# OpenROV_Controller_2_8.net
KiCad netlist of a schematic drawn in EAGLE
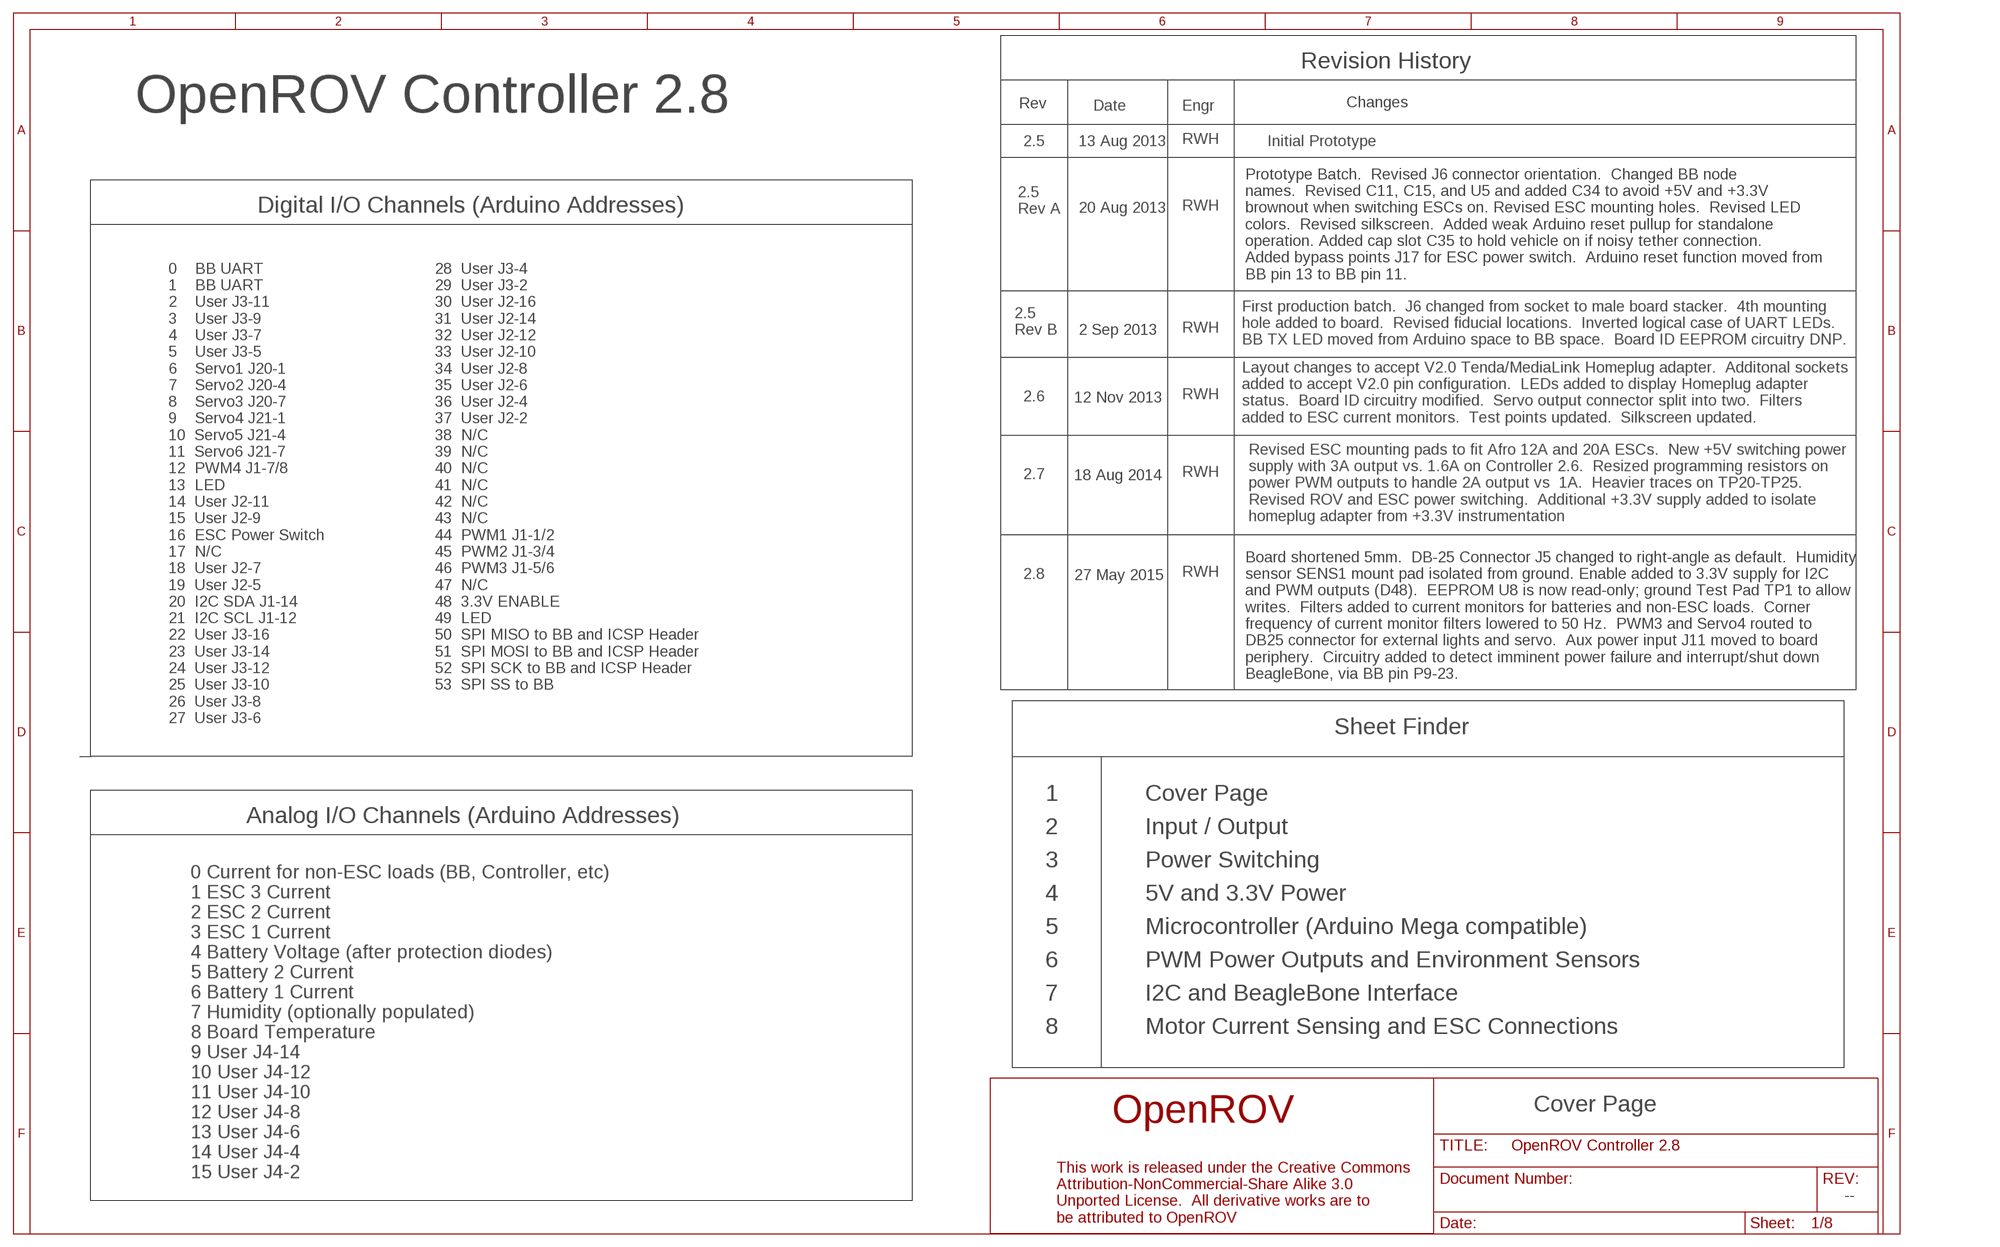
[diagram p0: schematic, sheet 1]
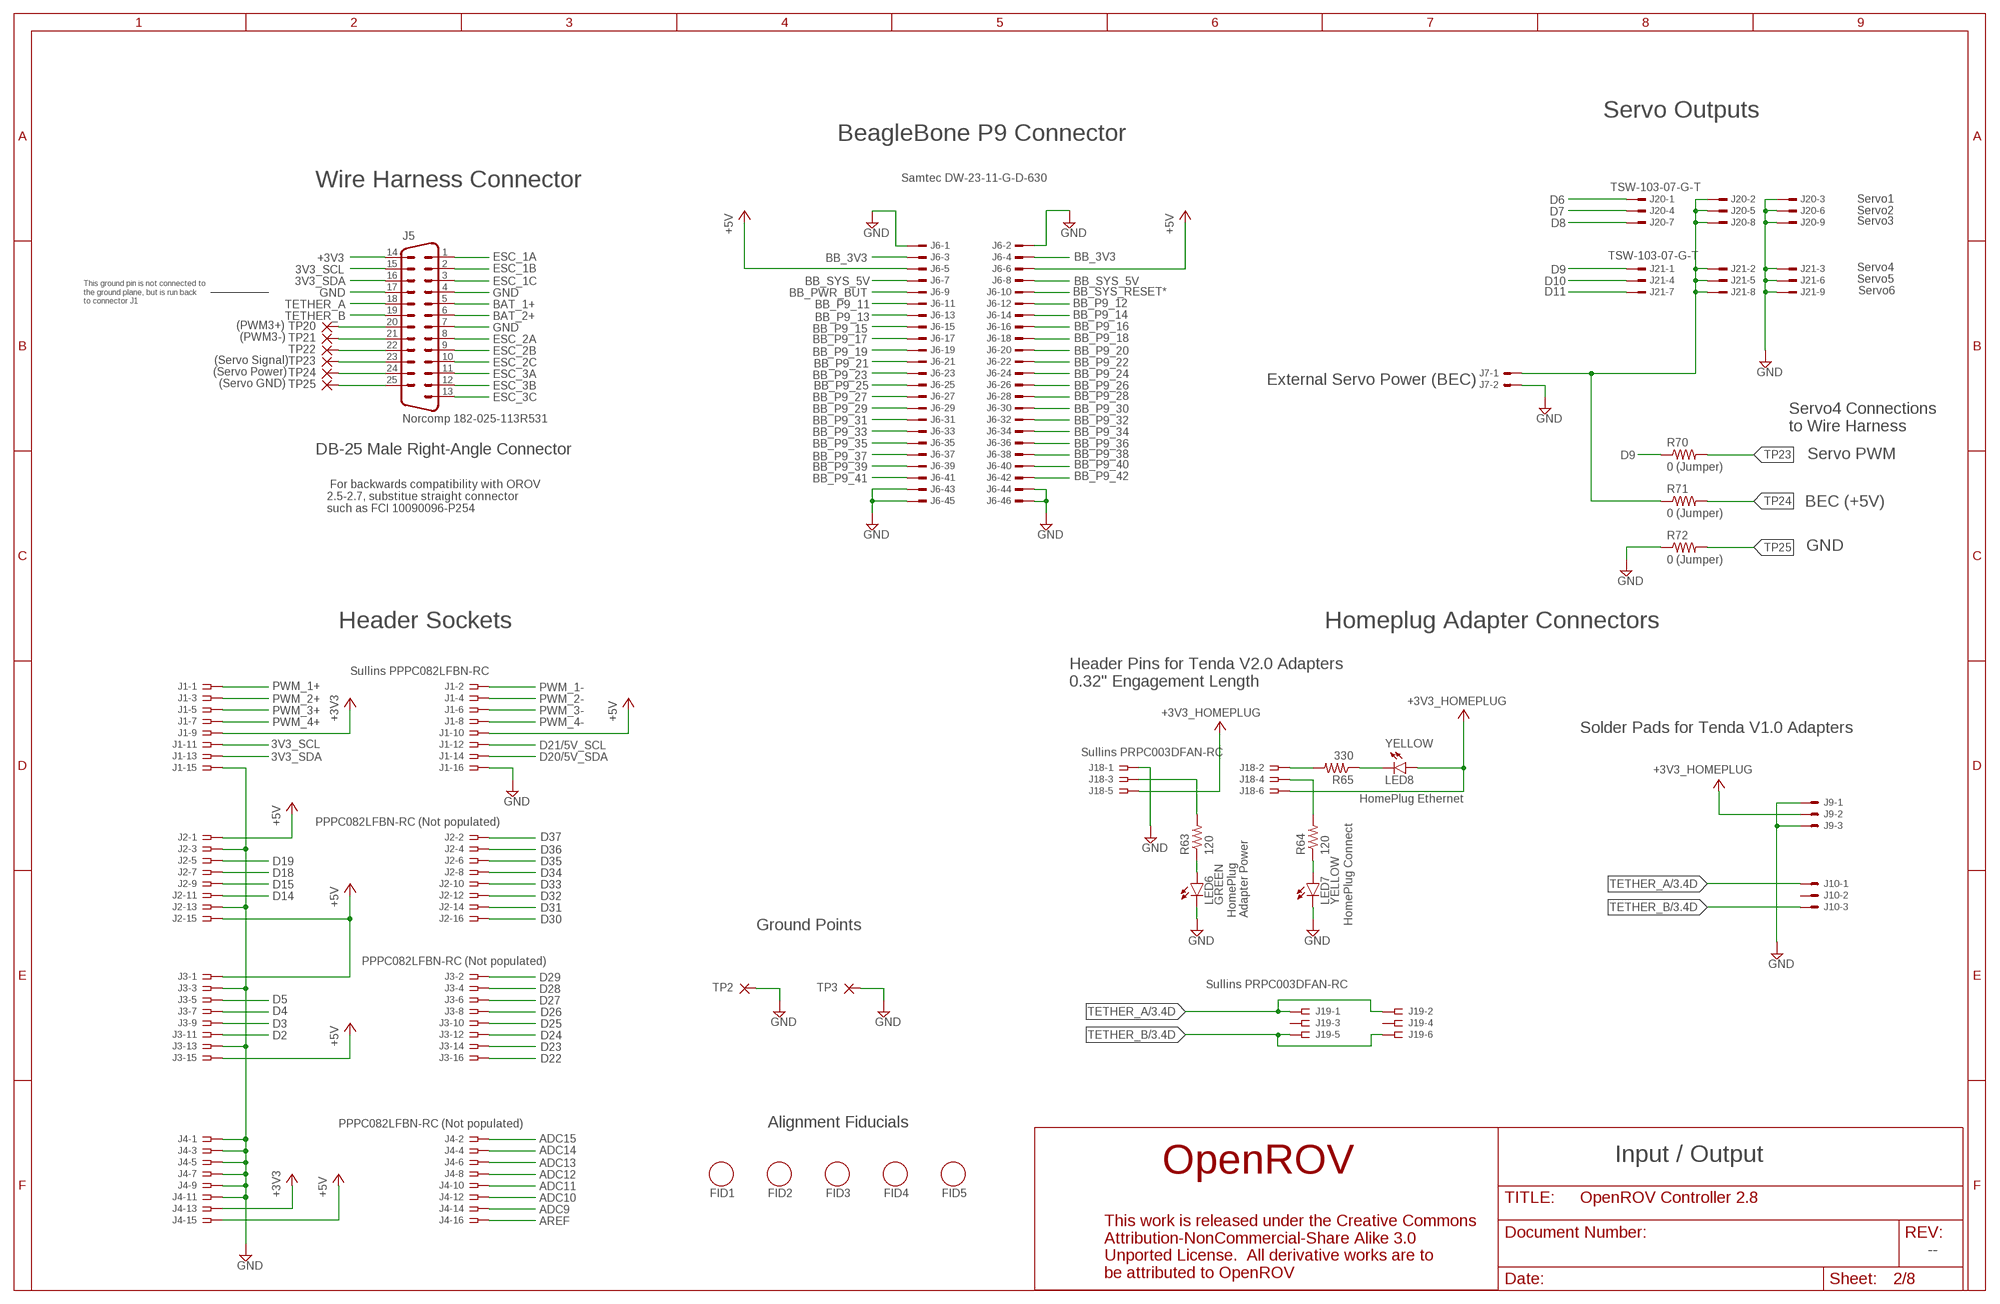
[diagram p1: schematic, sheet 2]
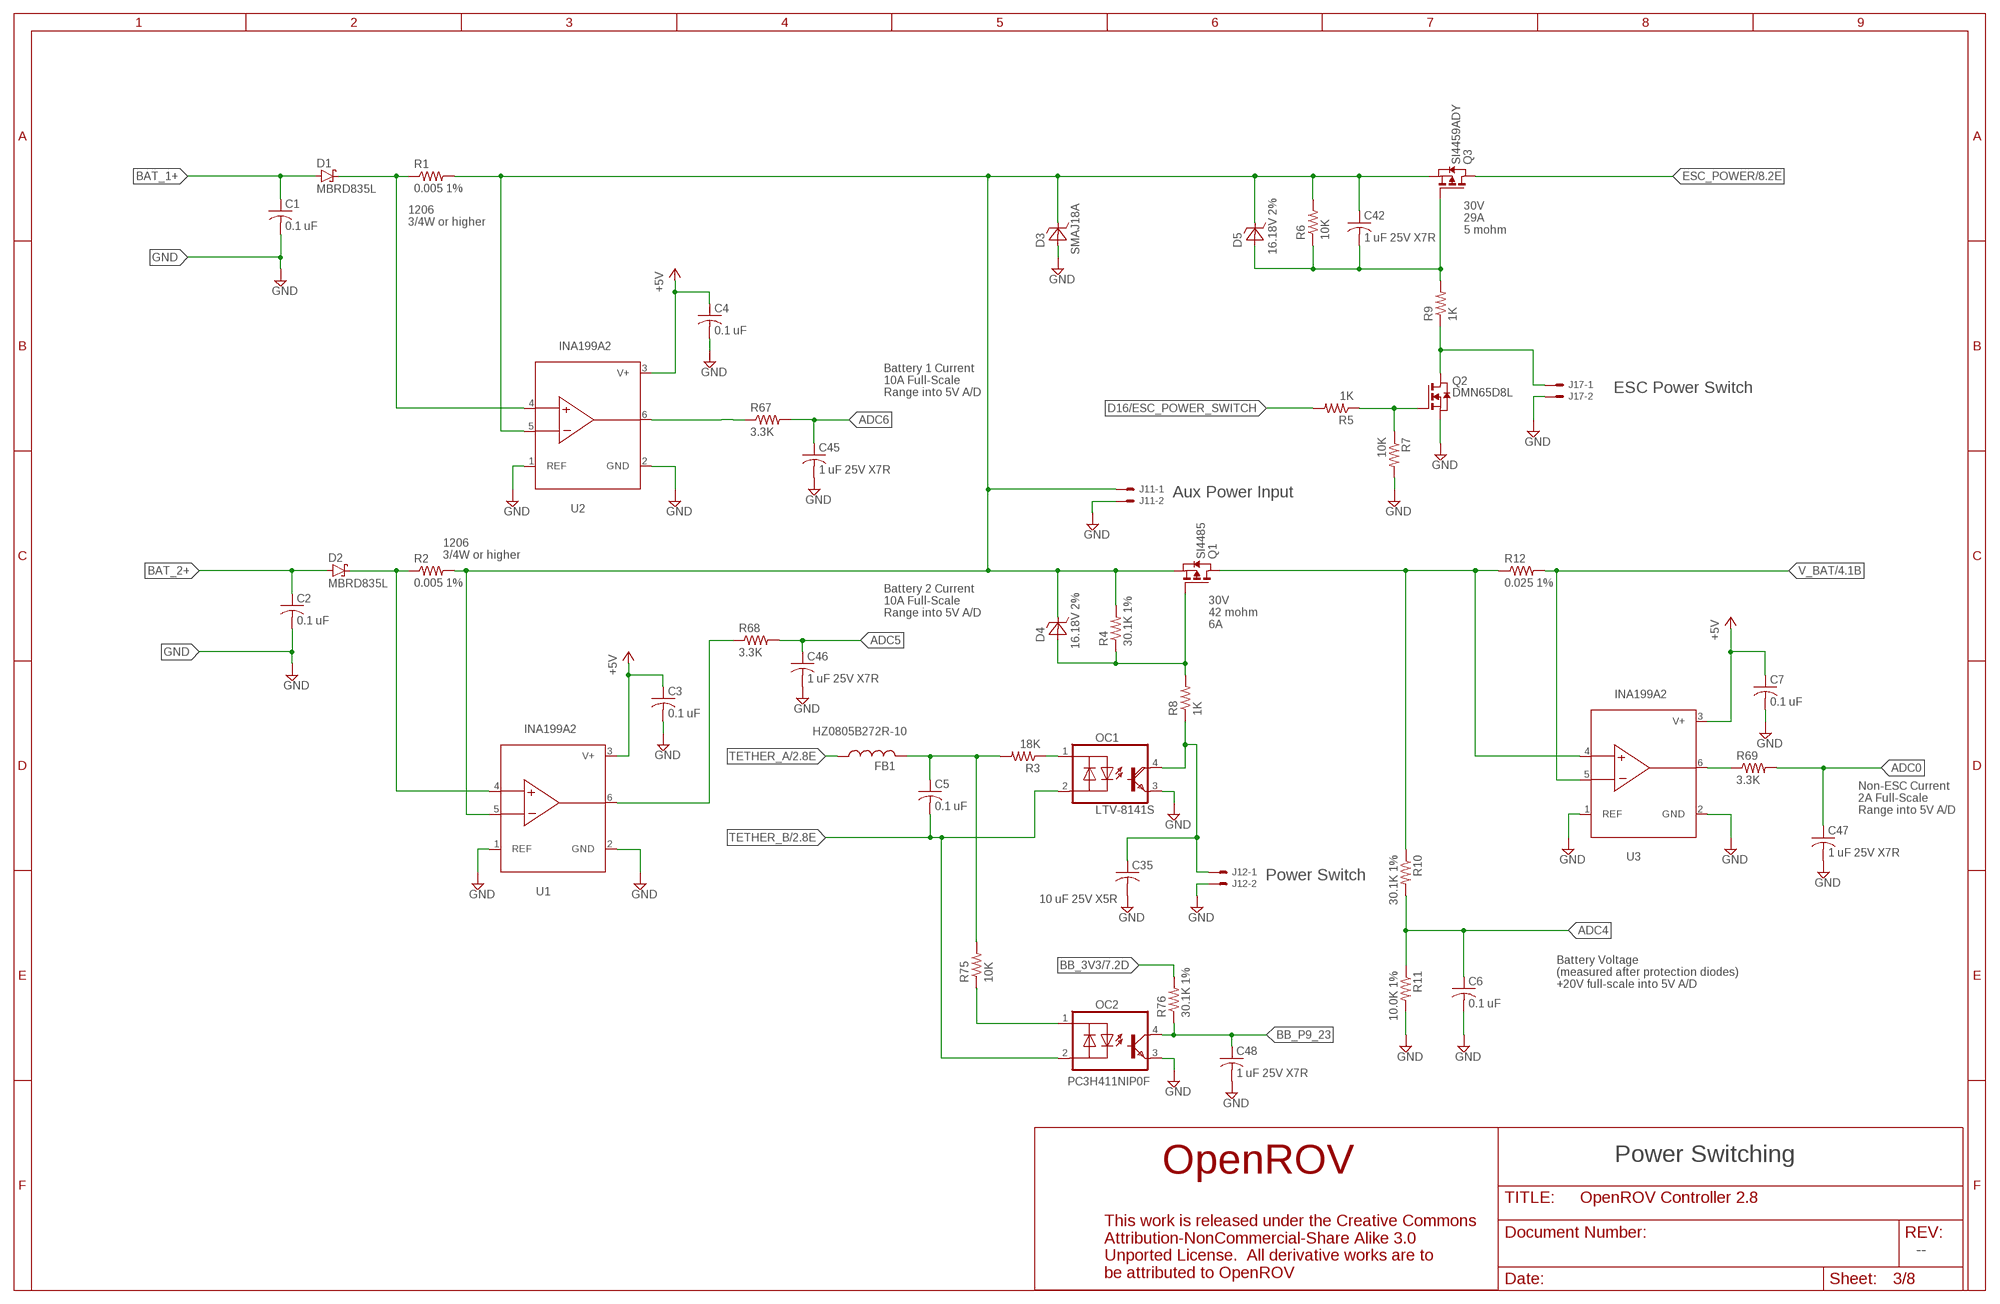
[diagram p2: schematic, sheet 3]
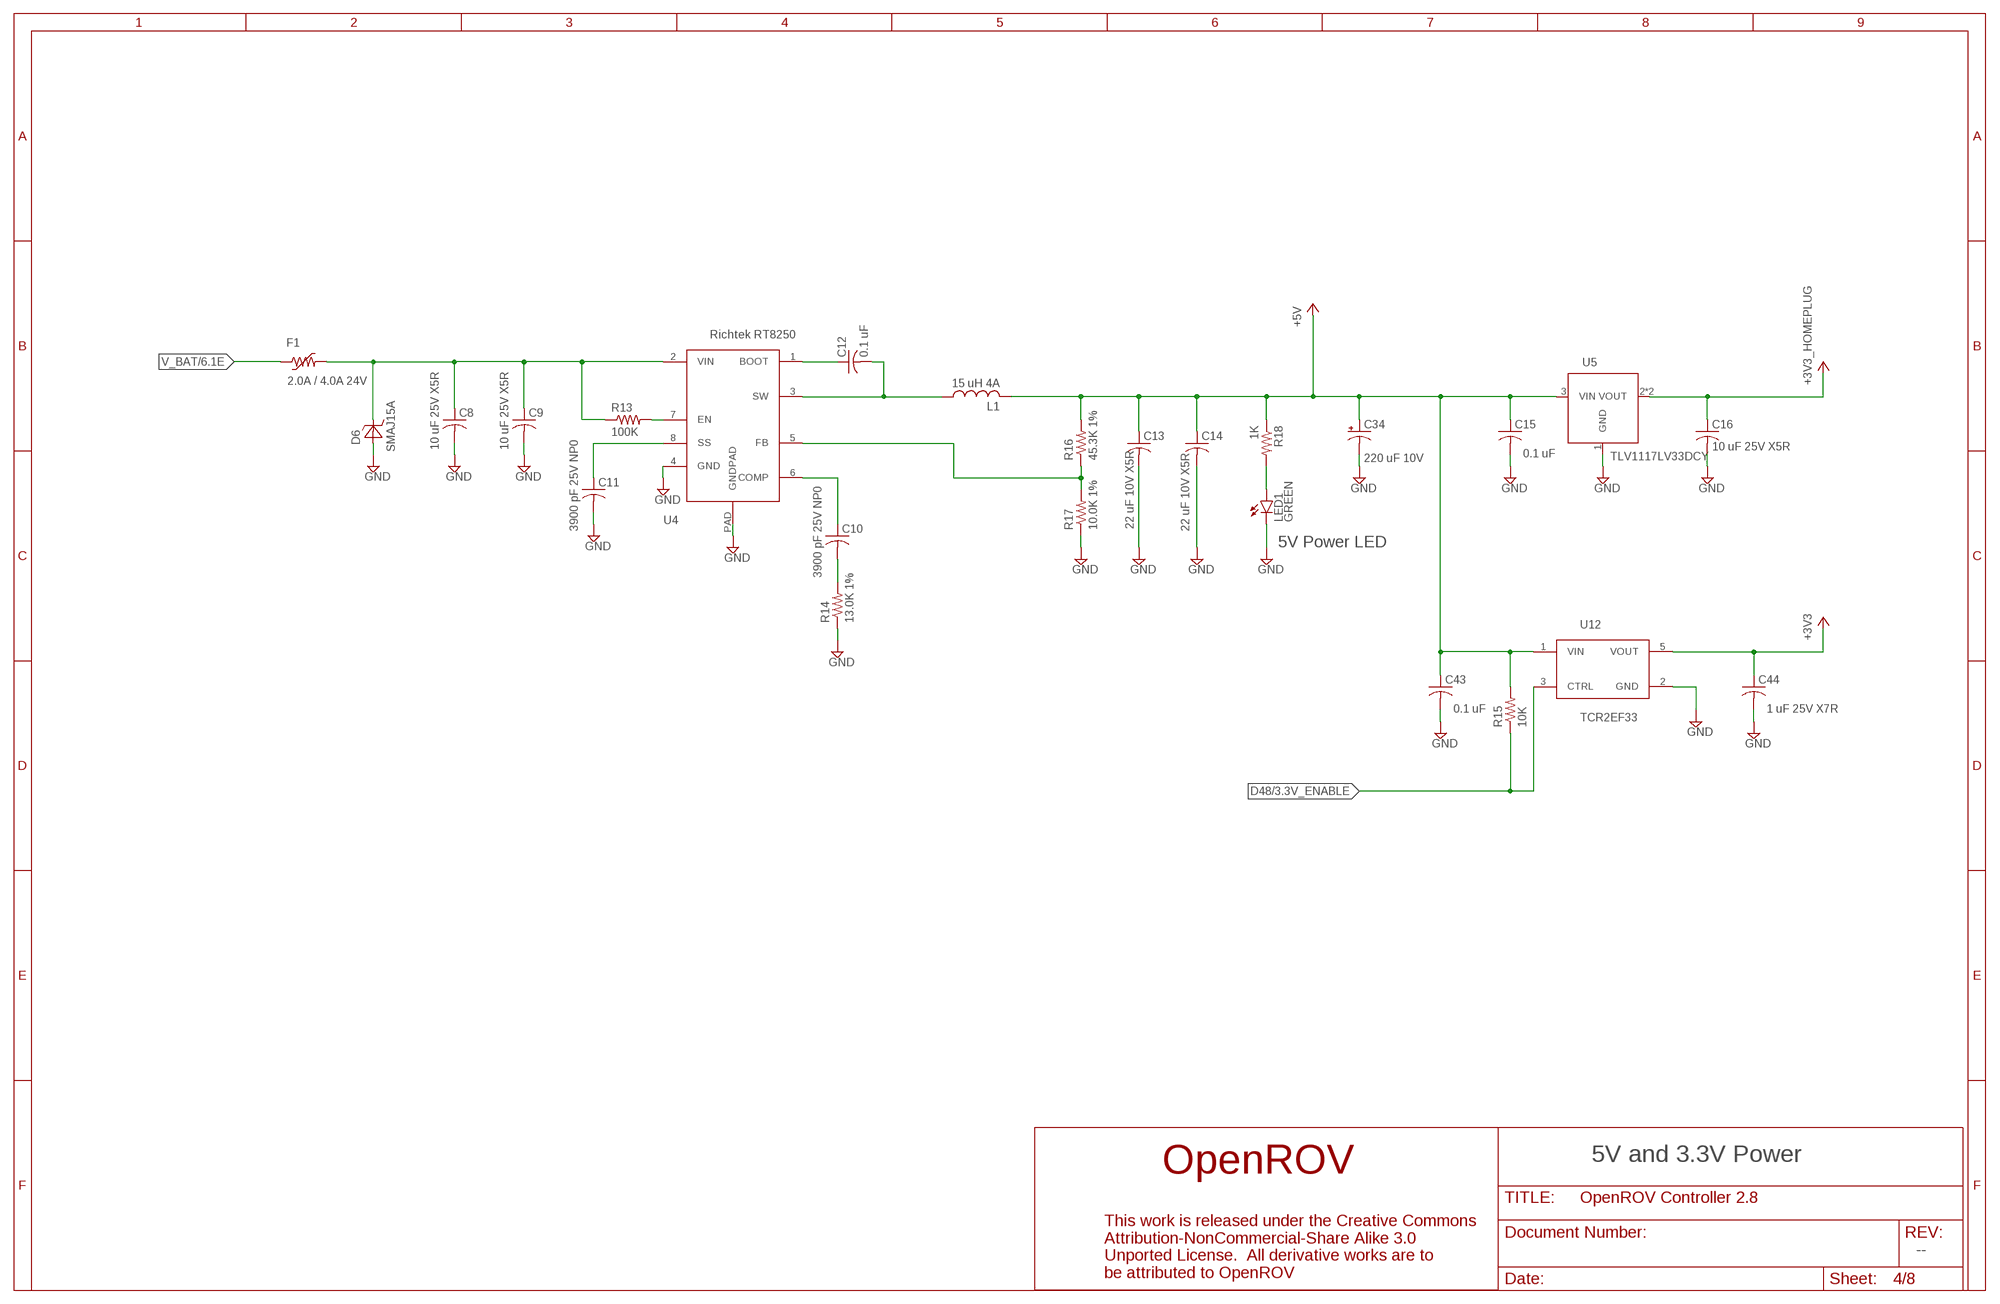
[diagram p3: schematic, sheet 4]
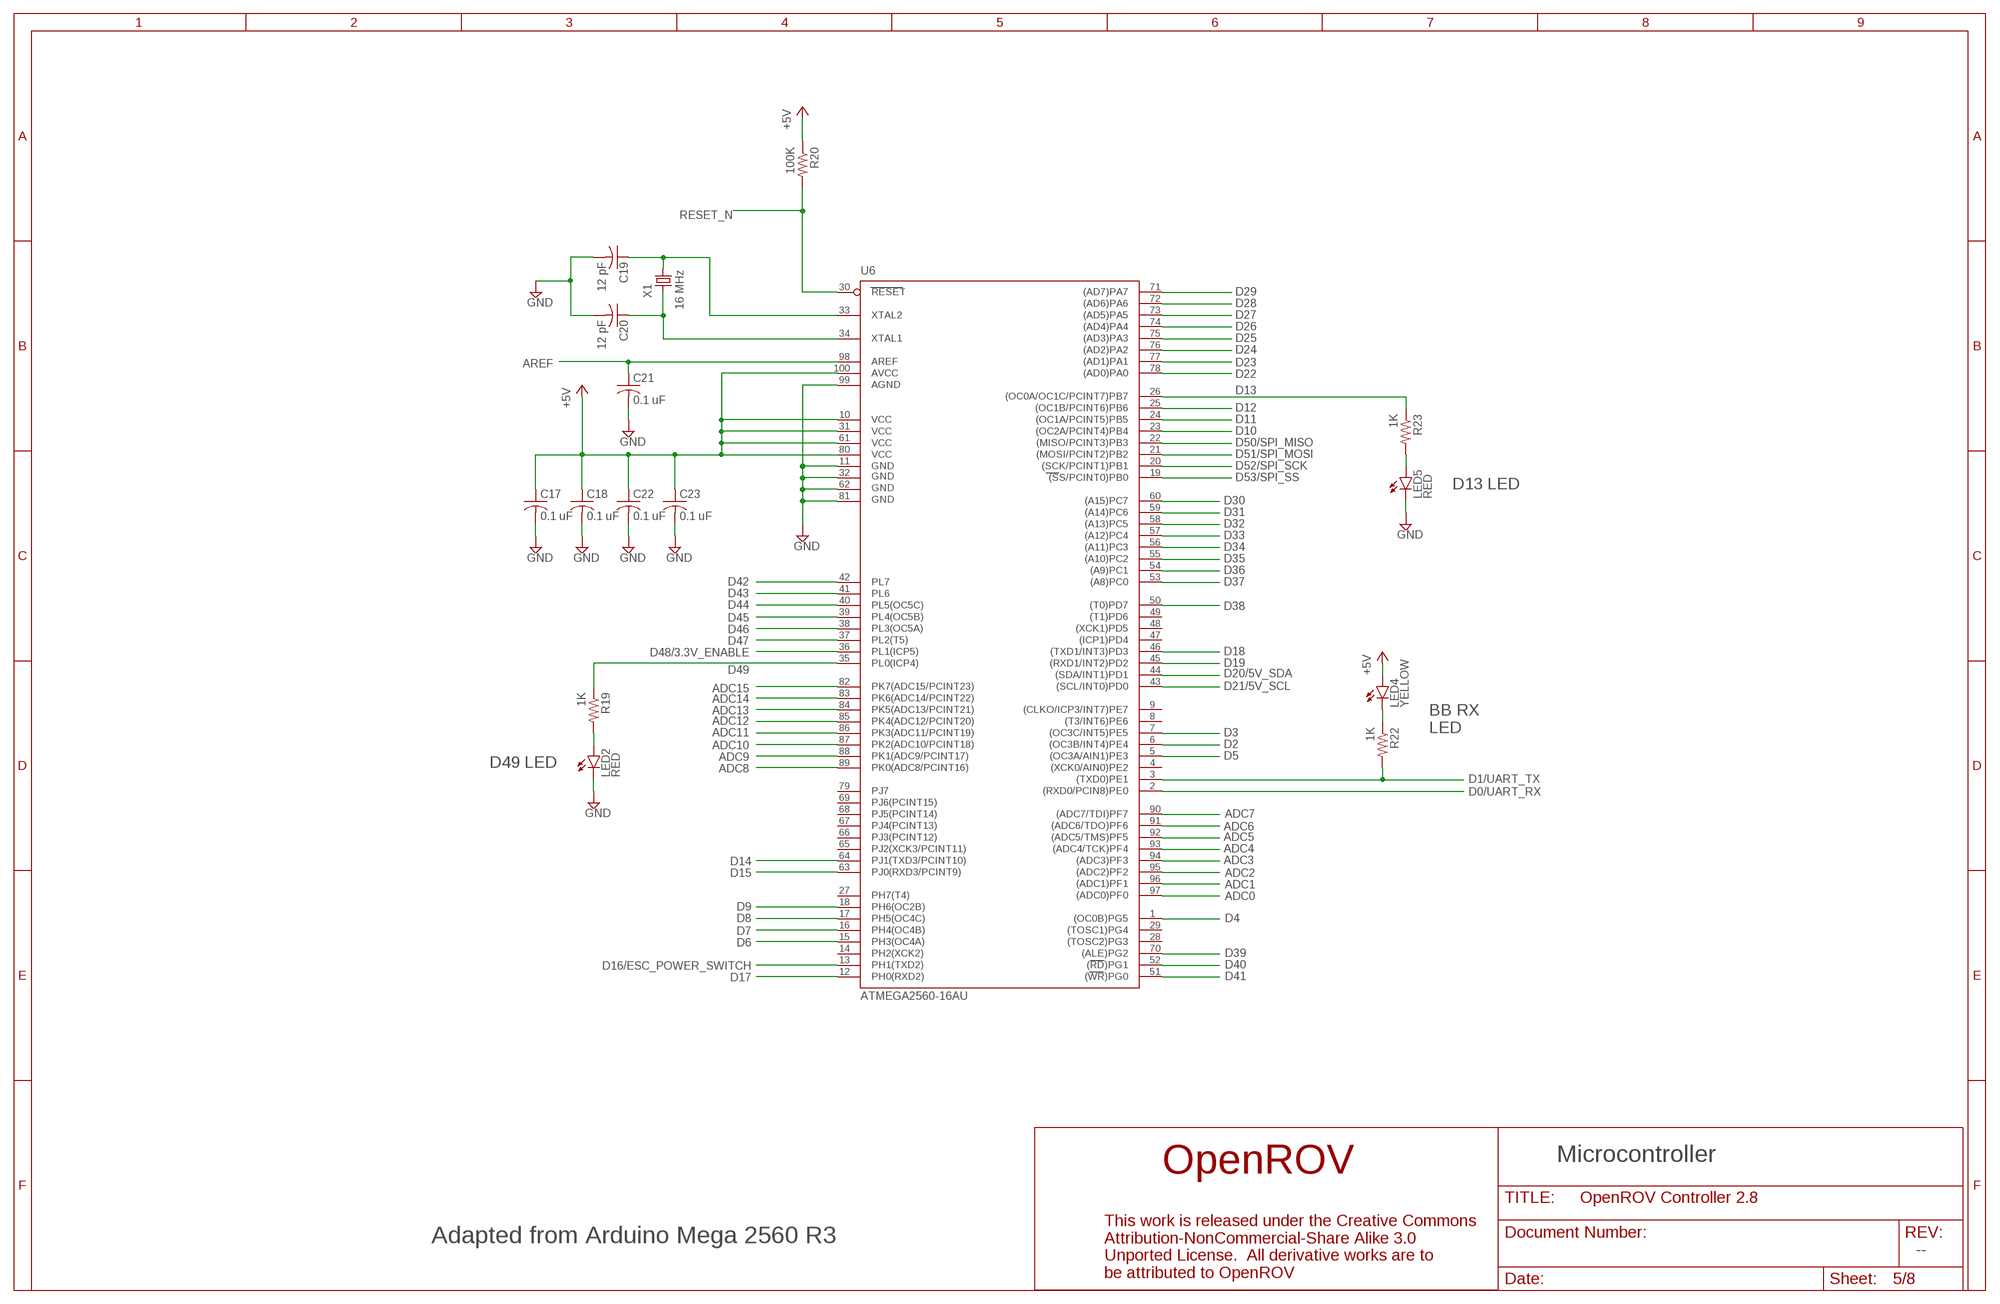
[diagram p4: schematic, sheet 5]
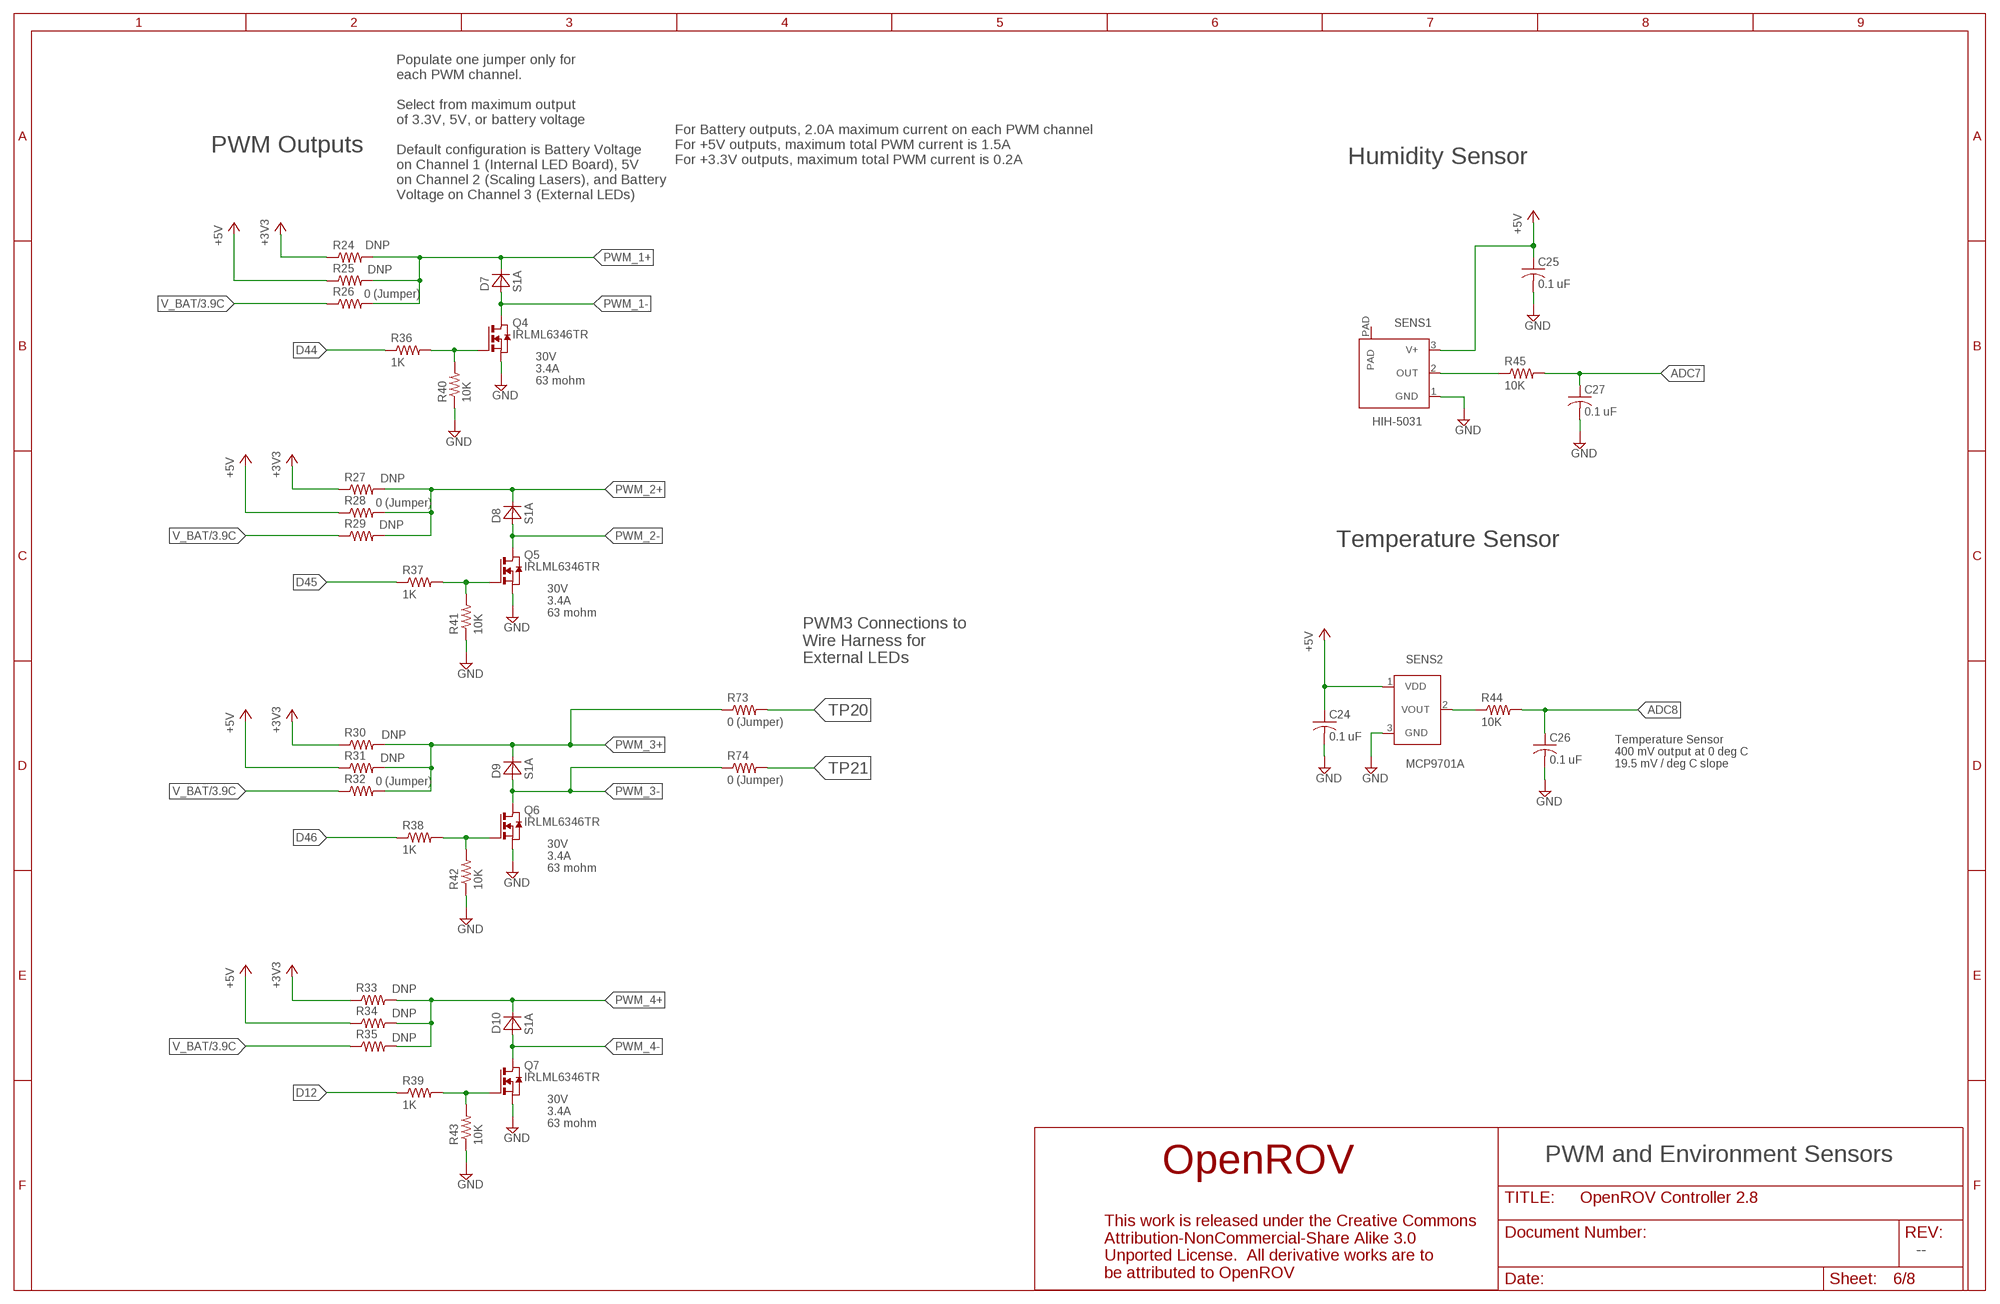
[diagram p5: schematic, sheet 6]
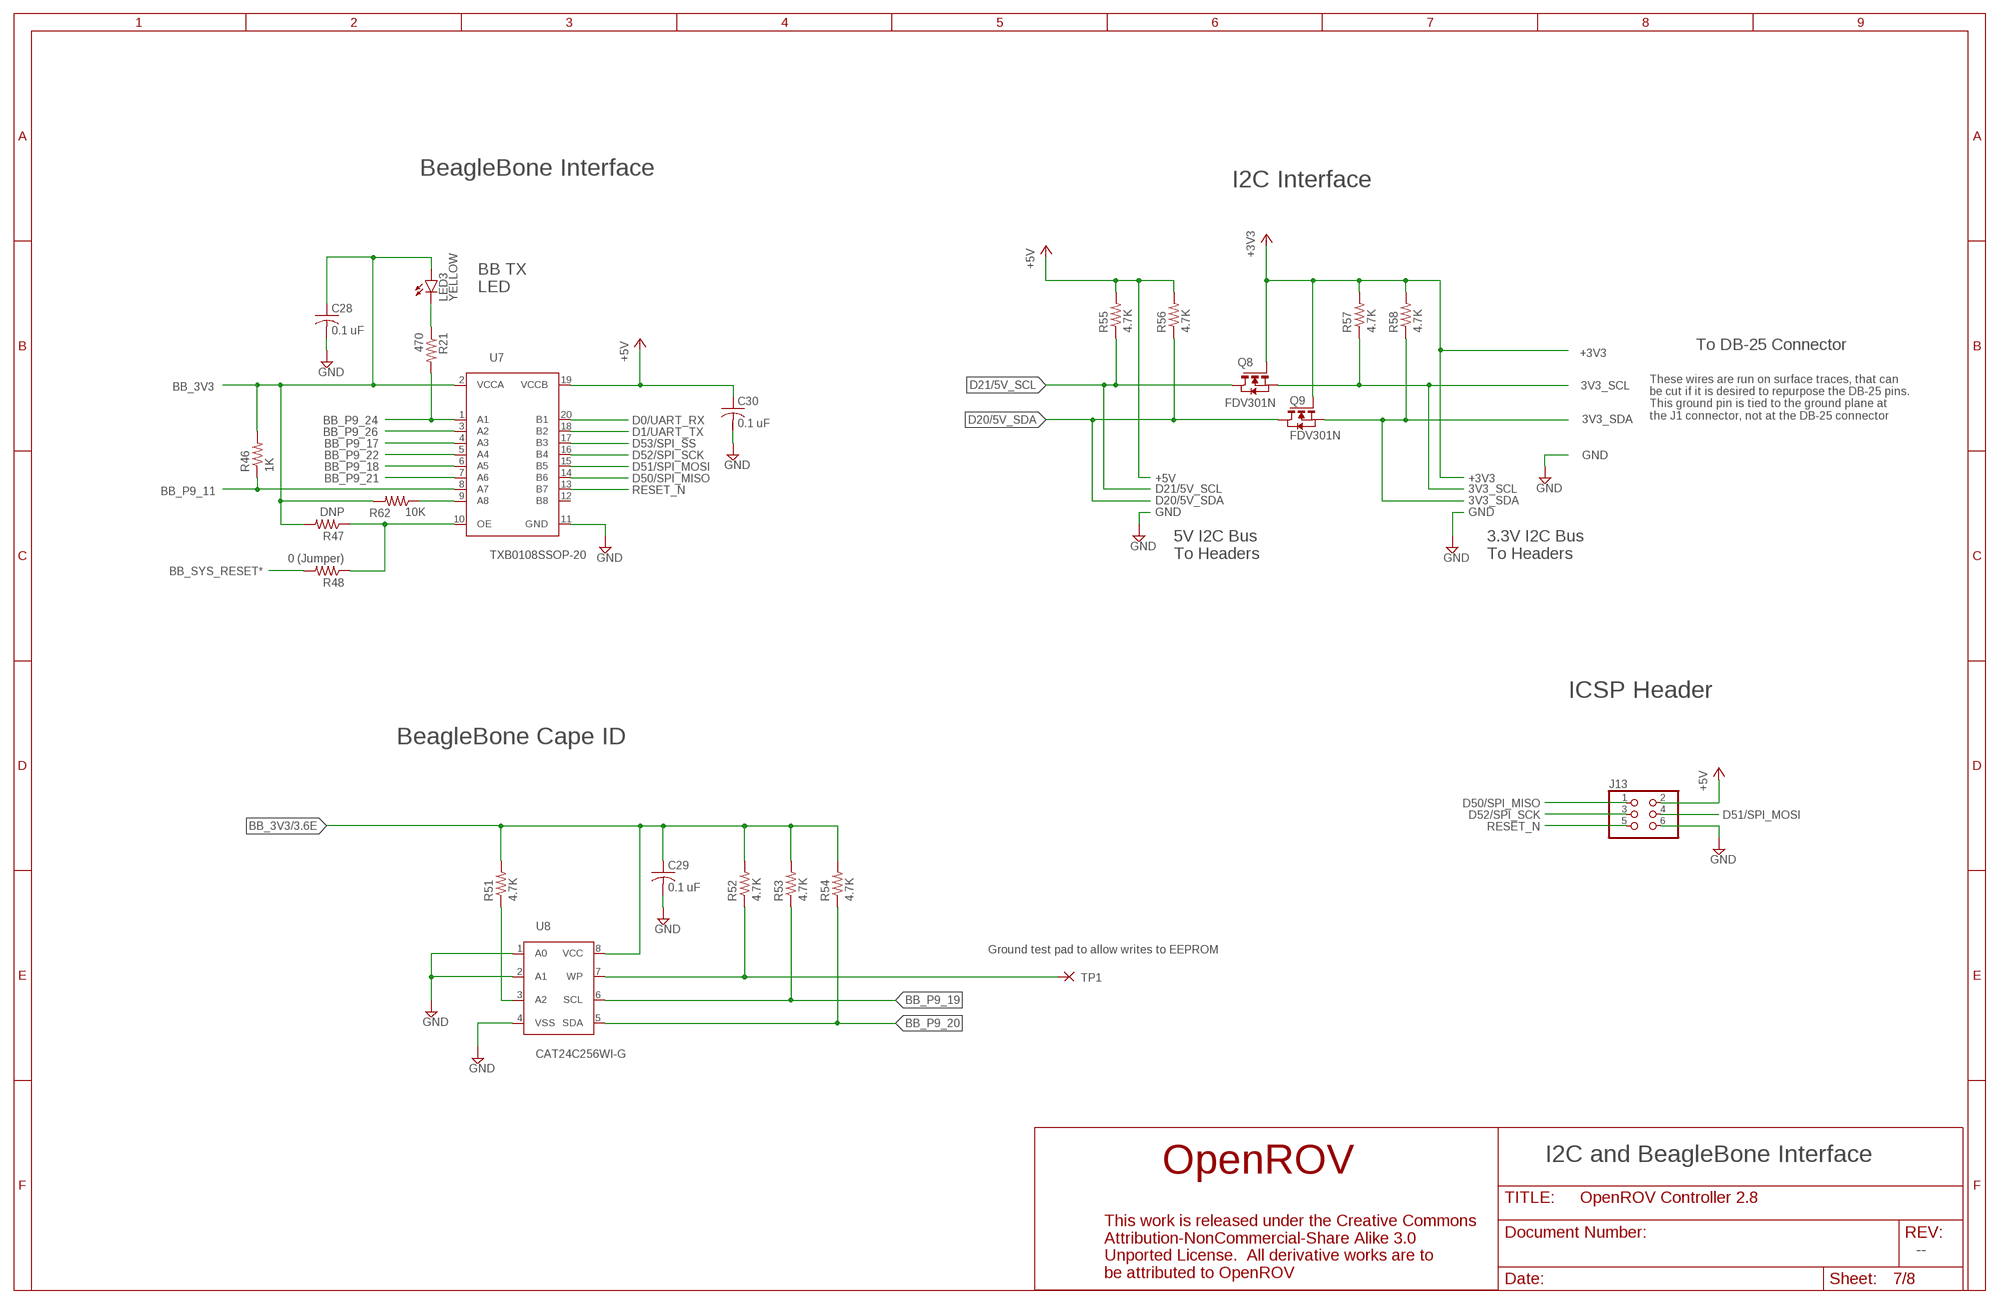
[diagram p6: schematic, sheet 7]
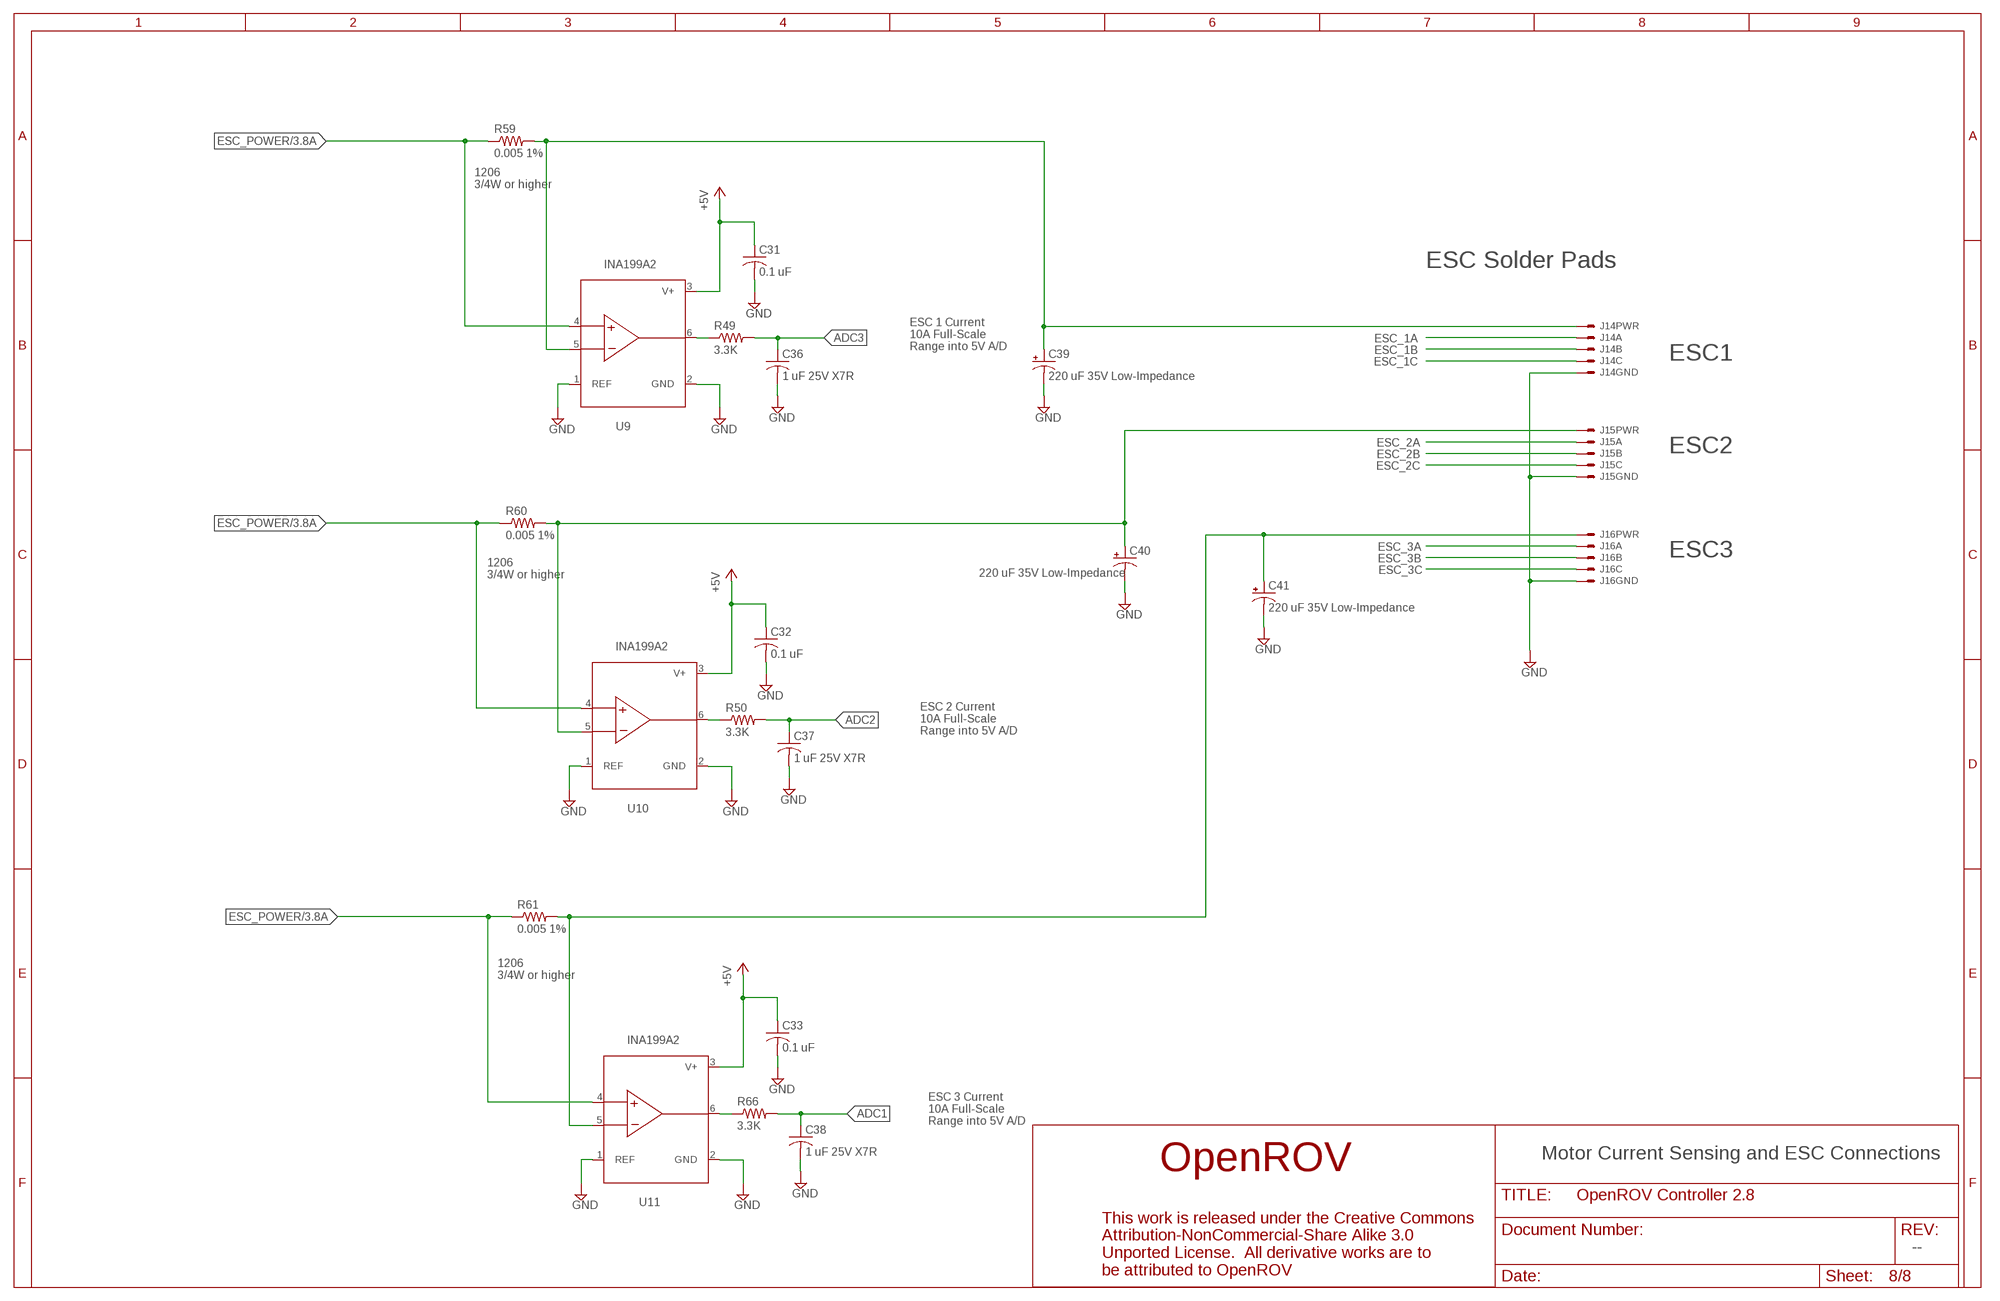
[diagram p7: schematic, sheet 8]

(export (version "E")
  (design (tool "Eeschema 10.0.6"))
  (components
    (comp (ref "C24")
      (value "0.1 uF")
      (footprint "eagle-import:R0603")
      (libsource (lib "eagle-import") (part "CAP0603"))
    )
    (comp (ref "C25")
      (value "0.1 uF")
      (footprint "eagle-import:R0603")
      (libsource (lib "eagle-import") (part "CAP0603"))
    )
    (comp (ref "C26")
      (value "0.1 uF")
      (footprint "eagle-import:R0603")
      (libsource (lib "eagle-import") (part "CAP0603"))
    )
    (comp (ref "C27")
      (value "0.1 uF")
      (footprint "eagle-import:R0603")
      (libsource (lib "eagle-import") (part "CAP0603"))
    )
    (comp (ref "D7")
      (value "S1A")
      (footprint "eagle-import:DO214AC")
      (libsource (lib "eagle-import") (part "DIODE"))
    )
    (comp (ref "D8")
      (value "S1A")
      (footprint "eagle-import:DO214AC")
      (libsource (lib "eagle-import") (part "DIODE"))
    )
    (comp (ref "D9")
      (value "S1A")
      (footprint "eagle-import:DO214AC")
      (libsource (lib "eagle-import") (part "DIODE"))
    )
    (comp (ref "D10")
      (value "S1A")
      (footprint "eagle-import:DO214AC")
      (libsource (lib "eagle-import") (part "DIODE"))
    )
    (comp (ref "Q4")
      (value "IRLML6346TR")
      (footprint "eagle-import:SOT23")
      (libsource (lib "eagle-import") (part "NMOS-FETSOT23"))
    )
    (comp (ref "Q5")
      (value "IRLML6346TR")
      (footprint "eagle-import:SOT23")
      (libsource (lib "eagle-import") (part "NMOS-FETSOT23"))
    )
    (comp (ref "Q6")
      (value "IRLML6346TR")
      (footprint "eagle-import:SOT23")
      (libsource (lib "eagle-import") (part "NMOS-FETSOT23"))
    )
    (comp (ref "Q7")
      (value "IRLML6346TR")
      (footprint "eagle-import:SOT23")
      (libsource (lib "eagle-import") (part "NMOS-FETSOT23"))
    )
    (comp (ref "R24")
      (value "DNP")
      (footprint "eagle-import:R0805")
      (libsource (lib "eagle-import") (part "RESISTOR-0805"))
    )
    (comp (ref "R25")
      (value "DNP")
      (footprint "eagle-import:R0805")
      (libsource (lib "eagle-import") (part "RESISTOR-0805"))
    )
    (comp (ref "R26")
      (value "0 (Jumper)")
      (footprint "eagle-import:R0805")
      (libsource (lib "eagle-import") (part "RESISTOR-0805"))
    )
    (comp (ref "R27")
      (value "DNP")
      (footprint "eagle-import:R0805")
      (libsource (lib "eagle-import") (part "RESISTOR-0805"))
    )
    (comp (ref "R28")
      (value "0 (Jumper)")
      (footprint "eagle-import:R0805")
      (libsource (lib "eagle-import") (part "RESISTOR-0805"))
    )
    (comp (ref "R29")
      (value "DNP")
      (footprint "eagle-import:R0805")
      (libsource (lib "eagle-import") (part "RESISTOR-0805"))
    )
    (comp (ref "R30")
      (value "DNP")
      (footprint "eagle-import:R0805")
      (libsource (lib "eagle-import") (part "RESISTOR-0805"))
    )
    (comp (ref "R31")
      (value "DNP")
      (footprint "eagle-import:R0805")
      (libsource (lib "eagle-import") (part "RESISTOR-0805"))
    )
    (comp (ref "R32")
      (value "0 (Jumper)")
      (footprint "eagle-import:R0805")
      (libsource (lib "eagle-import") (part "RESISTOR-0805"))
    )
    (comp (ref "R33")
      (value "DNP")
      (footprint "eagle-import:R0805")
      (libsource (lib "eagle-import") (part "RESISTOR-0805"))
    )
    (comp (ref "R34")
      (value "DNP")
      (footprint "eagle-import:R0805")
      (libsource (lib "eagle-import") (part "RESISTOR-0805"))
    )
    (comp (ref "R35")
      (value "DNP")
      (footprint "eagle-import:R0805")
      (libsource (lib "eagle-import") (part "RESISTOR-0805"))
    )
    (comp (ref "R36")
      (value "1K")
      (footprint "eagle-import:R0603")
      (libsource (lib "eagle-import") (part "RESISTOR-0603"))
    )
    (comp (ref "R37")
      (value "1K")
      (footprint "eagle-import:R0603")
      (libsource (lib "eagle-import") (part "RESISTOR-0603"))
    )
    (comp (ref "R38")
      (value "1K")
      (footprint "eagle-import:R0603")
      (libsource (lib "eagle-import") (part "RESISTOR-0603"))
    )
    (comp (ref "R39")
      (value "1K")
      (footprint "eagle-import:R0603")
      (libsource (lib "eagle-import") (part "RESISTOR-0603"))
    )
    (comp (ref "R40")
      (value "10K")
      (footprint "eagle-import:R0603")
      (libsource (lib "eagle-import") (part "RESISTOR-0603"))
    )
    (comp (ref "R41")
      (value "10K")
      (footprint "eagle-import:R0603")
      (libsource (lib "eagle-import") (part "RESISTOR-0603"))
    )
    (comp (ref "R42")
      (value "10K")
      (footprint "eagle-import:R0603")
      (libsource (lib "eagle-import") (part "RESISTOR-0603"))
    )
    (comp (ref "R43")
      (value "10K")
      (footprint "eagle-import:R0603")
      (libsource (lib "eagle-import") (part "RESISTOR-0603"))
    )
    (comp (ref "R44")
      (value "10K")
      (footprint "eagle-import:R0603")
      (libsource (lib "eagle-import") (part "RESISTOR-0603"))
    )
    (comp (ref "R45")
      (value "10K")
      (footprint "eagle-import:R0603")
      (libsource (lib "eagle-import") (part "RESISTOR-0603"))
    )
    (comp (ref "R73")
      (value "0 (Jumper)")
      (footprint "eagle-import:R0805")
      (libsource (lib "eagle-import") (part "RESISTOR-0805"))
    )
    (comp (ref "R74")
      (value "0 (Jumper)")
      (footprint "eagle-import:R0805")
      (libsource (lib "eagle-import") (part "RESISTOR-0805"))
    )
    (comp (ref "SENS1")
      (value "HIH-5031")
      (footprint "eagle-import:HIH-5031")
      (libsource (lib "eagle-import") (part "HIH-5031"))
    )
    (comp (ref "SENS2")
      (value "MCP9701A")
      (footprint "eagle-import:SOT23")
      (libsource (lib "eagle-import") (part "MCP9701"))
    )
    (comp (ref "C17")
      (value "0.1 uF")
      (footprint "eagle-import:R0603")
      (libsource (lib "eagle-import") (part "CAP0603"))
    )
    (comp (ref "C18")
      (value "0.1 uF")
      (footprint "eagle-import:R0603")
      (libsource (lib "eagle-import") (part "CAP0603"))
    )
    (comp (ref "C19")
      (value "12 pF")
      (footprint "eagle-import:R0603")
      (libsource (lib "eagle-import") (part "CAP0603"))
    )
    (comp (ref "C20")
      (value "12 pF")
      (footprint "eagle-import:R0603")
      (libsource (lib "eagle-import") (part "CAP0603"))
    )
    (comp (ref "C21")
      (value "0.1 uF")
      (footprint "eagle-import:R0603")
      (libsource (lib "eagle-import") (part "CAP0603"))
    )
    (comp (ref "C22")
      (value "0.1 uF")
      (footprint "eagle-import:R0603")
      (libsource (lib "eagle-import") (part "CAP0603"))
    )
    (comp (ref "C23")
      (value "0.1 uF")
      (footprint "eagle-import:R0603")
      (libsource (lib "eagle-import") (part "CAP0603"))
    )
    (comp (ref "LED2")
      (value "RED")
      (footprint "eagle-import:LED_CHIPLED_0603")
      (libsource (lib "eagle-import") (part "LED-0603"))
    )
    (comp (ref "LED4")
      (value "YELLOW")
      (footprint "eagle-import:LED_CHIPLED_0603")
      (libsource (lib "eagle-import") (part "LED-0603"))
    )
    (comp (ref "LED5")
      (value "RED")
      (footprint "eagle-import:LED_CHIPLED_0603")
      (libsource (lib "eagle-import") (part "LED-0603"))
    )
    (comp (ref "R19")
      (value "1K")
      (footprint "eagle-import:R0603")
      (libsource (lib "eagle-import") (part "RESISTOR-0603"))
    )
    (comp (ref "R20")
      (value "100K")
      (footprint "eagle-import:R0603")
      (libsource (lib "eagle-import") (part "RESISTOR-0603"))
    )
    (comp (ref "R22")
      (value "1K")
      (footprint "eagle-import:R0603")
      (libsource (lib "eagle-import") (part "RESISTOR-0603"))
    )
    (comp (ref "R23")
      (value "1K")
      (footprint "eagle-import:R0603")
      (libsource (lib "eagle-import") (part "RESISTOR-0603"))
    )
    (comp (ref "U6")
      (value "ATMEGA2560-16AU")
      (footprint "eagle-import:SMARTPRJ_TQFP100")
      (libsource (lib "eagle-import") (part "SMARTPRJ_ATMEGA2560AU2560-16"))
    )
    (comp (ref "X1")
      (value "16 MHz")
      (footprint "eagle-import:DISCRETE_2P-SMD-5X3.2")
      (libsource (lib "eagle-import") (part "CRYSTAL-53.2"))
    )
    (comp (ref "C8")
      (value "10 uF 25V X5R")
      (footprint "eagle-import:R0805")
      (libsource (lib "eagle-import") (part "CAP0805"))
    )
    (comp (ref "C9")
      (value "10 uF 25V X5R")
      (footprint "eagle-import:R0805")
      (libsource (lib "eagle-import") (part "CAP0805"))
    )
    (comp (ref "C10")
      (value "3900 pF 25V NP0")
      (footprint "eagle-import:R0603")
      (libsource (lib "eagle-import") (part "CAP0603"))
    )
    (comp (ref "C11")
      (value "3900 pF 25V NP0")
      (footprint "eagle-import:R0603")
      (libsource (lib "eagle-import") (part "CAP0603"))
    )
    (comp (ref "C12")
      (value "0.1 uF")
      (footprint "eagle-import:R0603")
      (libsource (lib "eagle-import") (part "CAP0603"))
    )
    (comp (ref "C13")
      (value "22 uF 10V X5R")
      (footprint "eagle-import:R0805")
      (libsource (lib "eagle-import") (part "CAP0805"))
    )
    (comp (ref "C14")
      (value "22 uF 10V X5R")
      (footprint "eagle-import:R0805")
      (libsource (lib "eagle-import") (part "CAP0805"))
    )
    (comp (ref "C15")
      (value "0.1 uF")
      (footprint "eagle-import:R0603")
      (libsource (lib "eagle-import") (part "CAP0603"))
    )
    (comp (ref "C16")
      (value "10 uF 25V X5R")
      (footprint "eagle-import:R0805")
      (libsource (lib "eagle-import") (part "CAP0805"))
    )
    (comp (ref "C34")
      (value "220 uF 10V")
      (footprint "eagle-import:NICHICON_8MM")
      (libsource (lib "eagle-import") (part "CAP-POLARIZED-NICHICON-8MM"))
    )
    (comp (ref "C43")
      (value "0.1 uF")
      (footprint "eagle-import:R0603")
      (libsource (lib "eagle-import") (part "CAP0603"))
    )
    (comp (ref "C44")
      (value "1 uF 25V X7R")
      (footprint "eagle-import:R0603")
      (libsource (lib "eagle-import") (part "CAP0603"))
    )
    (comp (ref "D6")
      (value "SMAJ15A")
      (footprint "eagle-import:DO214AC")
      (libsource (lib "eagle-import") (part "ZENER-TVSDO-214AC"))
    )
    (comp (ref "F1")
      (value "2.0A / 4.0A 24V")
      (footprint "eagle-import:R2920")
      (libsource (lib "eagle-import") (part "POLYFUSE-2920"))
    )
    (comp (ref "L1")
      (value "15 uH 4A")
      (footprint "eagle-import:INDUCTOR_BOURNS_12X0")
      (libsource (lib "eagle-import") (part "INDUCTOR-BOURNS-12X0"))
    )
    (comp (ref "LED1")
      (value "GREEN")
      (footprint "eagle-import:LED_CHIPLED_0603")
      (libsource (lib "eagle-import") (part "LED-0603"))
    )
    (comp (ref "R13")
      (value "100K")
      (footprint "eagle-import:R0603")
      (libsource (lib "eagle-import") (part "RESISTOR-0603"))
    )
    (comp (ref "R14")
      (value "13.0K 1%")
      (footprint "eagle-import:R0603")
      (libsource (lib "eagle-import") (part "RESISTOR-0603"))
    )
    (comp (ref "R15")
      (value "10K")
      (footprint "eagle-import:R0603")
      (libsource (lib "eagle-import") (part "RESISTOR-0603"))
    )
    (comp (ref "R16")
      (value "45.3K 1%")
      (footprint "eagle-import:R0603")
      (libsource (lib "eagle-import") (part "RESISTOR-0603"))
    )
    (comp (ref "R17")
      (value "10.0K 1%")
      (footprint "eagle-import:R0603")
      (libsource (lib "eagle-import") (part "RESISTOR-0603"))
    )
    (comp (ref "R18")
      (value "1K")
      (footprint "eagle-import:R0603")
      (libsource (lib "eagle-import") (part "RESISTOR-0603"))
    )
    (comp (ref "U4")
      (value "Richtek RT8250")
      (footprint "eagle-import:SO8-THERMAL")
      (libsource (lib "eagle-import") (part "RICHTEK_82XX"))
    )
    (comp (ref "U5")
      (value "TLV1117LV33DCY")
      (footprint "eagle-import:SOT223")
      (libsource (lib "eagle-import") (part "AP1117SOT223"))
    )
    (comp (ref "U12")
      (value "TCR2EF33")
      (footprint "eagle-import:SOT23-5L")
      (libsource (lib "eagle-import") (part "TCR2EF"))
    )
    (comp (ref "C28")
      (value "0.1 uF")
      (footprint "eagle-import:R0603")
      (libsource (lib "eagle-import") (part "CAP0603"))
    )
    (comp (ref "C29")
      (value "0.1 uF")
      (footprint "eagle-import:R0603")
      (libsource (lib "eagle-import") (part "CAP0603"))
    )
    (comp (ref "C30")
      (value "0.1 uF")
      (footprint "eagle-import:R0603")
      (libsource (lib "eagle-import") (part "CAP0603"))
    )
    (comp (ref "J13")
      (value "HDR_PINS_2X3")
      (footprint "eagle-import:HDR_PINS_2X3")
      (libsource (lib "eagle-import") (part "HDR_PINS_2X3"))
    )
    (comp (ref "LED3")
      (value "YELLOW")
      (footprint "eagle-import:LED_CHIPLED_0603")
      (libsource (lib "eagle-import") (part "LED-0603"))
    )
    (comp (ref "Q8")
      (value "FDV301N")
      (footprint "eagle-import:SOT23")
      (libsource (lib "eagle-import") (part "NMOS-FETSOT23"))
    )
    (comp (ref "Q9")
      (value "FDV301N")
      (footprint "eagle-import:SOT23")
      (libsource (lib "eagle-import") (part "NMOS-FETSOT23"))
    )
    (comp (ref "R21")
      (value "470")
      (footprint "eagle-import:R0603")
      (libsource (lib "eagle-import") (part "RESISTOR-0603"))
    )
    (comp (ref "R46")
      (value "1K")
      (footprint "eagle-import:R0603")
      (libsource (lib "eagle-import") (part "RESISTOR-0603"))
    )
    (comp (ref "R47")
      (value "DNP")
      (footprint "eagle-import:R0603")
      (libsource (lib "eagle-import") (part "RESISTOR-0603"))
    )
    (comp (ref "R48")
      (value "0 (Jumper)")
      (footprint "eagle-import:R0603")
      (libsource (lib "eagle-import") (part "RESISTOR-0603"))
    )
    (comp (ref "R51")
      (value "4.7K")
      (footprint "eagle-import:R0603")
      (libsource (lib "eagle-import") (part "RESISTOR-0603"))
    )
    (comp (ref "R52")
      (value "4.7K")
      (footprint "eagle-import:R0603")
      (libsource (lib "eagle-import") (part "RESISTOR-0603"))
    )
    (comp (ref "R53")
      (value "4.7K")
      (footprint "eagle-import:R0603")
      (libsource (lib "eagle-import") (part "RESISTOR-0603"))
    )
    (comp (ref "R54")
      (value "4.7K")
      (footprint "eagle-import:R0603")
      (libsource (lib "eagle-import") (part "RESISTOR-0603"))
    )
    (comp (ref "R55")
      (value "4.7K")
      (footprint "eagle-import:R0603")
      (libsource (lib "eagle-import") (part "RESISTOR-0603"))
    )
    (comp (ref "R56")
      (value "4.7K")
      (footprint "eagle-import:R0603")
      (libsource (lib "eagle-import") (part "RESISTOR-0603"))
    )
    (comp (ref "R57")
      (value "4.7K")
      (footprint "eagle-import:R0603")
      (libsource (lib "eagle-import") (part "RESISTOR-0603"))
    )
    (comp (ref "R58")
      (value "4.7K")
      (footprint "eagle-import:R0603")
      (libsource (lib "eagle-import") (part "RESISTOR-0603"))
    )
    (comp (ref "R62")
      (value "10K")
      (footprint "eagle-import:R0603")
      (libsource (lib "eagle-import") (part "RESISTOR-0603"))
    )
    (comp (ref "TP1")
      (value "TEST_PAD-1.0")
      (footprint "eagle-import:2.0_1.0")
      (libsource (lib "eagle-import") (part "TEST_PAD-1.0"))
    )
    (comp (ref "U7")
      (value "TXB0108SSOP-20")
      (footprint "eagle-import:SSOP-20")
      (libsource (lib "eagle-import") (part "TXB0108SSOP-20"))
    )
    (comp (ref "U8")
      (value "CAT24C256WI-G")
      (footprint "eagle-import:SO8")
      (libsource (lib "eagle-import") (part "CAT24C256WI-G"))
    )
    (comp (ref "C1")
      (value "0.1 uF")
      (footprint "eagle-import:R0603")
      (libsource (lib "eagle-import") (part "CAP0603"))
    )
    (comp (ref "C2")
      (value "0.1 uF")
      (footprint "eagle-import:R0603")
      (libsource (lib "eagle-import") (part "CAP0603"))
    )
    (comp (ref "C3")
      (value "0.1 uF")
      (footprint "eagle-import:R0603")
      (libsource (lib "eagle-import") (part "CAP0603"))
    )
    (comp (ref "C4")
      (value "0.1 uF")
      (footprint "eagle-import:R0603")
      (libsource (lib "eagle-import") (part "CAP0603"))
    )
    (comp (ref "C5")
      (value "0.1 uF")
      (footprint "eagle-import:R0603")
      (libsource (lib "eagle-import") (part "CAP0603"))
    )
    (comp (ref "C6")
      (value "0.1 uF")
      (footprint "eagle-import:R0603")
      (libsource (lib "eagle-import") (part "CAP0603"))
    )
    (comp (ref "C7")
      (value "0.1 uF")
      (footprint "eagle-import:R0603")
      (libsource (lib "eagle-import") (part "CAP0603"))
    )
    (comp (ref "C35")
      (value "10 uF 25V X5R")
      (footprint "eagle-import:R0805")
      (libsource (lib "eagle-import") (part "CAP0805"))
    )
    (comp (ref "C42")
      (value "1 uF 25V X7R")
      (footprint "eagle-import:R0603")
      (libsource (lib "eagle-import") (part "CAP0603"))
    )
    (comp (ref "C45")
      (value "1 uF 25V X7R")
      (footprint "eagle-import:R0603")
      (libsource (lib "eagle-import") (part "CAP0603"))
    )
    (comp (ref "C46")
      (value "1 uF 25V X7R")
      (footprint "eagle-import:R0603")
      (libsource (lib "eagle-import") (part "CAP0603"))
    )
    (comp (ref "C47")
      (value "1 uF 25V X7R")
      (footprint "eagle-import:R0603")
      (libsource (lib "eagle-import") (part "CAP0603"))
    )
    (comp (ref "C48")
      (value "1 uF 25V X7R")
      (footprint "eagle-import:R0603")
      (libsource (lib "eagle-import") (part "CAP0603"))
    )
    (comp (ref "D1")
      (value "MBRD835L")
      (footprint "eagle-import:DPAK")
      (libsource (lib "eagle-import") (part "SCHOTTKYDPAK"))
    )
    (comp (ref "D2")
      (value "MBRD835L")
      (footprint "eagle-import:DPAK")
      (libsource (lib "eagle-import") (part "SCHOTTKYDPAK"))
    )
    (comp (ref "D3")
      (value "SMAJ18A")
      (footprint "eagle-import:DO214AC")
      (libsource (lib "eagle-import") (part "ZENER-TVSDO-214AC"))
    )
    (comp (ref "D4")
      (value "16.18V 2%")
      (footprint "eagle-import:SOD323")
      (libsource (lib "eagle-import") (part "ZENER-TVSSOD323"))
    )
    (comp (ref "D5")
      (value "16.18V 2%")
      (footprint "eagle-import:SOD323")
      (libsource (lib "eagle-import") (part "ZENER-TVSSOD323"))
    )
    (comp (ref "FB1")
      (value "HZ0805B272R-10")
      (footprint "eagle-import:R0805")
      (libsource (lib "eagle-import") (part "FERRITESIZE_0805"))
    )
    (comp (ref "J11")
      (value "HDR_1X2X0.100-ALT_SILK")
      (footprint "eagle-import:22-23-2021_ALT_SILK")
      (libsource (lib "eagle-import") (part "HDR_1X2X0.100-ALT_SILK"))
    )
    (comp (ref "J12")
      (value "HDR_1X2X0.100-ALT_SILK")
      (footprint "eagle-import:22-23-2021_ALT_SILK")
      (libsource (lib "eagle-import") (part "HDR_1X2X0.100-ALT_SILK"))
    )
    (comp (ref "J17")
      (value "HDR_1X2X0.100-ALT_SILK")
      (footprint "eagle-import:22-23-2021_ALT_SILK")
      (libsource (lib "eagle-import") (part "HDR_1X2X0.100-ALT_SILK"))
    )
    (comp (ref "OC1")
      (value "LTV-8141S")
      (footprint "eagle-import:DIL4-SMD")
      (libsource (lib "eagle-import") (part "LTV-8141S"))
    )
    (comp (ref "OC2")
      (value "PC3H411NIP0F")
      (footprint "eagle-import:OPTOCOUPLER-MINIFLAT-HALFPITCH")
      (libsource (lib "eagle-import") (part "OPTOCOUPLER-TRANSISTOR-BIDIR-MINIFLAT-HALFPITCH"))
    )
    (comp (ref "Q1")
      (value "SI4485")
      (footprint "eagle-import:SO8")
      (libsource (lib "eagle-import") (part "PMOS-FET"))
    )
    (comp (ref "Q2")
      (value "DMN65D8L")
      (footprint "eagle-import:SOT23")
      (libsource (lib "eagle-import") (part "NMOS-FETSOT23"))
    )
    (comp (ref "Q3")
      (value "SI4459ADY")
      (footprint "eagle-import:SO8")
      (libsource (lib "eagle-import") (part "PMOS-FET"))
    )
    (comp (ref "R1")
      (value "0.005 1%")
      (footprint "eagle-import:R1206")
      (libsource (lib "eagle-import") (part "RESISTOR-1206"))
    )
    (comp (ref "R2")
      (value "0.005 1%")
      (footprint "eagle-import:R1206")
      (libsource (lib "eagle-import") (part "RESISTOR-1206"))
    )
    (comp (ref "R3")
      (value "18K")
      (footprint "eagle-import:R0603")
      (libsource (lib "eagle-import") (part "RESISTOR-0603"))
    )
    (comp (ref "R4")
      (value "30.1K 1%")
      (footprint "eagle-import:R0603")
      (libsource (lib "eagle-import") (part "RESISTOR-0603"))
    )
    (comp (ref "R5")
      (value "1K")
      (footprint "eagle-import:R0603")
      (libsource (lib "eagle-import") (part "RESISTOR-0603"))
    )
    (comp (ref "R6")
      (value "10K")
      (footprint "eagle-import:R0603")
      (libsource (lib "eagle-import") (part "RESISTOR-0603"))
    )
    (comp (ref "R7")
      (value "10K")
      (footprint "eagle-import:R0603")
      (libsource (lib "eagle-import") (part "RESISTOR-0603"))
    )
    (comp (ref "R8")
      (value "1K")
      (footprint "eagle-import:R0603")
      (libsource (lib "eagle-import") (part "RESISTOR-0603"))
    )
    (comp (ref "R9")
      (value "1K")
      (footprint "eagle-import:R0603")
      (libsource (lib "eagle-import") (part "RESISTOR-0603"))
    )
    (comp (ref "R10")
      (value "30.1K 1%")
      (footprint "eagle-import:R0603")
      (libsource (lib "eagle-import") (part "RESISTOR-0603"))
    )
    (comp (ref "R11")
      (value "10.0K 1%")
      (footprint "eagle-import:R0603")
      (libsource (lib "eagle-import") (part "RESISTOR-0603"))
    )
    (comp (ref "R12")
      (value "0.025 1%")
      (footprint "eagle-import:R0805")
      (libsource (lib "eagle-import") (part "RESISTOR-0805"))
    )
    (comp (ref "R67")
      (value "3.3K")
      (footprint "eagle-import:R0603")
      (libsource (lib "eagle-import") (part "RESISTOR-0603"))
    )
    (comp (ref "R68")
      (value "3.3K")
      (footprint "eagle-import:R0603")
      (libsource (lib "eagle-import") (part "RESISTOR-0603"))
    )
    (comp (ref "R69")
      (value "3.3K")
      (footprint "eagle-import:R0603")
      (libsource (lib "eagle-import") (part "RESISTOR-0603"))
    )
    (comp (ref "R75")
      (value "10K")
      (footprint "eagle-import:R0603")
      (libsource (lib "eagle-import") (part "RESISTOR-0603"))
    )
    (comp (ref "R76")
      (value "30.1K 1%")
      (footprint "eagle-import:R0603")
      (libsource (lib "eagle-import") (part "RESISTOR-0603"))
    )
    (comp (ref "U1")
      (value "INA199A2")
      (footprint "eagle-import:SC70-6L")
      (libsource (lib "eagle-import") (part "INA199"))
    )
    (comp (ref "U2")
      (value "INA199A2")
      (footprint "eagle-import:SC70-6L")
      (libsource (lib "eagle-import") (part "INA199"))
    )
    (comp (ref "U3")
      (value "INA199A2")
      (footprint "eagle-import:SC70-6L")
      (libsource (lib "eagle-import") (part "INA199"))
    )
    (comp (ref "FID1")
      (value "FIDUCIAL_1")
      (footprint "eagle-import:FIDUCIAL_1")
      (libsource (lib "eagle-import") (part "FIDUCIAL_1"))
    )
    (comp (ref "FID2")
      (value "FIDUCIAL_1")
      (footprint "eagle-import:FIDUCIAL_1")
      (libsource (lib "eagle-import") (part "FIDUCIAL_1"))
    )
    (comp (ref "FID3")
      (value "FIDUCIAL_1")
      (footprint "eagle-import:FIDUCIAL_1")
      (libsource (lib "eagle-import") (part "FIDUCIAL_1"))
    )
    (comp (ref "FID4")
      (value "FIDUCIAL_1")
      (footprint "eagle-import:FIDUCIAL_1")
      (libsource (lib "eagle-import") (part "FIDUCIAL_1"))
    )
    (comp (ref "FID5")
      (value "FIDUCIAL_1")
      (footprint "eagle-import:FIDUCIAL_1")
      (libsource (lib "eagle-import") (part "FIDUCIAL_1"))
    )
    (comp (ref "J1")
      (value "Sullins PPPC082LFBN-RC")
      (footprint "eagle-import:SSW-108-02-S-D")
      (fields (field (name "MPN") "SSW-108-02-S-D"))
      (libsource (lib "eagle-import") (part "HDR_SOCKET_2X8"))
    )
    (comp (ref "J2")
      (value "PPPC082LFBN-RC (Not populated)")
      (footprint "eagle-import:SSW-108-02-S-D")
      (fields (field (name "MPN") "SSW-108-02-S-D"))
      (libsource (lib "eagle-import") (part "HDR_SOCKET_2X8"))
    )
    (comp (ref "J3")
      (value "PPPC082LFBN-RC (Not populated)")
      (footprint "eagle-import:SSW-108-02-S-D")
      (fields (field (name "MPN") "SSW-108-02-S-D"))
      (libsource (lib "eagle-import") (part "HDR_SOCKET_2X8"))
    )
    (comp (ref "J4")
      (value "PPPC082LFBN-RC (Not populated)")
      (footprint "eagle-import:SSW-108-02-S-D")
      (fields (field (name "MPN") "SSW-108-02-S-D"))
      (libsource (lib "eagle-import") (part "HDR_SOCKET_2X8"))
    )
    (comp (ref "J5")
      (value "Norcomp 182-025-113R531")
      (footprint "eagle-import:M25VP")
      (libsource (lib "eagle-import") (part "M25VP"))
    )
    (comp (ref "J6")
      (value "Samtec DW-23-11-G-D-630")
      (footprint "eagle-import:TSW-123-02-S-D")
      (libsource (lib "eagle-import") (part "BEAGLEBONE_PIN_HEADER"))
    )
    (comp (ref "J7")
      (value "HDR_1X2X0.100-ALT_SILK")
      (footprint "eagle-import:22-23-2021_ALT_SILK")
      (libsource (lib "eagle-import") (part "HDR_1X2X0.100-ALT_SILK"))
    )
    (comp (ref "J9")
      (value "HDR_1X3X0.100-ALT_SILK")
      (footprint "eagle-import:22-23-2031_ALT_SILK")
      (libsource (lib "eagle-import") (part "HDR_1X3X0.100-ALT_SILK"))
    )
    (comp (ref "J10")
      (value "HDR_1X3X0.100-ALT_SILK")
      (footprint "eagle-import:22-23-2031_ALT_SILK")
      (libsource (lib "eagle-import") (part "HDR_1X3X0.100-ALT_SILK"))
    )
    (comp (ref "J18")
      (value "Sullins PRPC003DFAN-RC")
      (footprint "eagle-import:SSW-103-02-S-D")
      (fields (field (name "MPN") "SSW-103-02-S-D"))
      (libsource (lib "eagle-import") (part "HDR_SOCKET_2X3"))
    )
    (comp (ref "J19")
      (value "Sullins PRPC003DFAN-RC")
      (footprint "eagle-import:SSW-103-02-S-D")
      (fields (field (name "MPN") "SSW-103-02-S-D"))
      (libsource (lib "eagle-import") (part "HDR_SOCKET_2X3"))
    )
    (comp (ref "J20")
      (value "TSW-103-07-G-T")
      (footprint "eagle-import:HDR_PINS_3X3")
      (libsource (lib "eagle-import") (part "HDR_PINS_3X3{dblquote}"))
    )
    (comp (ref "J21")
      (value "TSW-103-07-G-T")
      (footprint "eagle-import:HDR_PINS_3X3")
      (libsource (lib "eagle-import") (part "HDR_PINS_3X3{dblquote}"))
    )
    (comp (ref "LED6")
      (value "GREEN")
      (footprint "eagle-import:LED_CHIPLED_0603")
      (libsource (lib "eagle-import") (part "LED-0603"))
    )
    (comp (ref "LED7")
      (value "YELLOW")
      (footprint "eagle-import:LED_CHIPLED_0603")
      (libsource (lib "eagle-import") (part "LED-0603"))
    )
    (comp (ref "LED8")
      (value "YELLOW")
      (footprint "eagle-import:LED_CHIPLED_0603")
      (libsource (lib "eagle-import") (part "LED-0603"))
    )
    (comp (ref "R63")
      (value "120")
      (footprint "eagle-import:R0603")
      (libsource (lib "eagle-import") (part "RESISTOR-0603"))
    )
    (comp (ref "R64")
      (value "120")
      (footprint "eagle-import:R0603")
      (libsource (lib "eagle-import") (part "RESISTOR-0603"))
    )
    (comp (ref "R65")
      (value "330")
      (footprint "eagle-import:R0603")
      (libsource (lib "eagle-import") (part "RESISTOR-0603"))
    )
    (comp (ref "R70")
      (value "0 (Jumper)")
      (footprint "eagle-import:R0805")
      (libsource (lib "eagle-import") (part "RESISTOR-0805"))
    )
    (comp (ref "R71")
      (value "0 (Jumper)")
      (footprint "eagle-import:R0805")
      (libsource (lib "eagle-import") (part "RESISTOR-0805"))
    )
    (comp (ref "R72")
      (value "0 (Jumper)")
      (footprint "eagle-import:R0805")
      (libsource (lib "eagle-import") (part "RESISTOR-0805"))
    )
    (comp (ref "TP2")
      (value "TEST_PAD-1.0")
      (footprint "eagle-import:2.0_1.0")
      (libsource (lib "eagle-import") (part "TEST_PAD-1.0"))
    )
    (comp (ref "TP3")
      (value "TEST_PAD-1.0")
      (footprint "eagle-import:2.0_1.0")
      (libsource (lib "eagle-import") (part "TEST_PAD-1.0"))
    )
    (comp (ref "TP20")
      (value "TEST_PAD-1.0")
      (footprint "eagle-import:2.0_1.0")
      (libsource (lib "eagle-import") (part "TEST_PAD-1.0"))
    )
    (comp (ref "TP21")
      (value "TEST_PAD-1.0")
      (footprint "eagle-import:2.0_1.0")
      (libsource (lib "eagle-import") (part "TEST_PAD-1.0"))
    )
    (comp (ref "TP22")
      (value "TEST_PAD-1.0")
      (footprint "eagle-import:2.0_1.0")
      (libsource (lib "eagle-import") (part "TEST_PAD-1.0"))
    )
    (comp (ref "TP23")
      (value "TEST_PAD-1.0")
      (footprint "eagle-import:2.0_1.0")
      (libsource (lib "eagle-import") (part "TEST_PAD-1.0"))
    )
    (comp (ref "TP24")
      (value "TEST_PAD-1.0")
      (footprint "eagle-import:2.0_1.0")
      (libsource (lib "eagle-import") (part "TEST_PAD-1.0"))
    )
    (comp (ref "TP25")
      (value "TEST_PAD-1.0")
      (footprint "eagle-import:2.0_1.0")
      (libsource (lib "eagle-import") (part "TEST_PAD-1.0"))
    )
    (comp (ref "C31")
      (value "0.1 uF")
      (footprint "eagle-import:R0603")
      (libsource (lib "eagle-import") (part "CAP0603"))
    )
    (comp (ref "C32")
      (value "0.1 uF")
      (footprint "eagle-import:R0603")
      (libsource (lib "eagle-import") (part "CAP0603"))
    )
    (comp (ref "C33")
      (value "0.1 uF")
      (footprint "eagle-import:R0603")
      (libsource (lib "eagle-import") (part "CAP0603"))
    )
    (comp (ref "C36")
      (value "1 uF 25V X7R")
      (footprint "eagle-import:R0603")
      (libsource (lib "eagle-import") (part "CAP0603"))
    )
    (comp (ref "C37")
      (value "1 uF 25V X7R")
      (footprint "eagle-import:R0603")
      (libsource (lib "eagle-import") (part "CAP0603"))
    )
    (comp (ref "C38")
      (value "1 uF 25V X7R")
      (footprint "eagle-import:R0603")
      (libsource (lib "eagle-import") (part "CAP0603"))
    )
    (comp (ref "C39")
      (value "220 uF 35V Low-Impedance")
      (footprint "eagle-import:NICHICON_10MM")
      (libsource (lib "eagle-import") (part "CAP-POLARIZED-NICHICON-10MM"))
    )
    (comp (ref "C40")
      (value "220 uF 35V Low-Impedance")
      (footprint "eagle-import:NICHICON_10MM")
      (libsource (lib "eagle-import") (part "CAP-POLARIZED-NICHICON-10MM"))
    )
    (comp (ref "C41")
      (value "220 uF 35V Low-Impedance")
      (footprint "eagle-import:NICHICON_10MM")
      (libsource (lib "eagle-import") (part "CAP-POLARIZED-NICHICON-10MM"))
    )
    (comp (ref "J14")
      (value "ESC_PADS-AFRO-12/20A-ESC1S")
      (footprint "eagle-import:AFRO-ESC-12_20A-ESC1S")
      (libsource (lib "eagle-import") (part "ESC_PADS-AFRO-12/20A-ESC1S"))
    )
    (comp (ref "J15")
      (value "ESC_PADS-AFRO-12/20A-ESC2S")
      (footprint "eagle-import:AFRO-ESC-12_20A-ESC2S")
      (libsource (lib "eagle-import") (part "ESC_PADS-AFRO-12/20A-ESC2S"))
    )
    (comp (ref "J16")
      (value "ESC_PADS-AFRO-12/20A-ESC3S")
      (footprint "eagle-import:AFRO-ESC-12_20A-ESC3S")
      (libsource (lib "eagle-import") (part "ESC_PADS-AFRO-12/20A-ESC3S"))
    )
    (comp (ref "R49")
      (value "3.3K")
      (footprint "eagle-import:R0603")
      (libsource (lib "eagle-import") (part "RESISTOR-0603"))
    )
    (comp (ref "R50")
      (value "3.3K")
      (footprint "eagle-import:R0603")
      (libsource (lib "eagle-import") (part "RESISTOR-0603"))
    )
    (comp (ref "R59")
      (value "0.005 1%")
      (footprint "eagle-import:R1206")
      (libsource (lib "eagle-import") (part "RESISTOR-1206"))
    )
    (comp (ref "R60")
      (value "0.005 1%")
      (footprint "eagle-import:R1206")
      (libsource (lib "eagle-import") (part "RESISTOR-1206"))
    )
    (comp (ref "R61")
      (value "0.005 1%")
      (footprint "eagle-import:R1206")
      (libsource (lib "eagle-import") (part "RESISTOR-1206"))
    )
    (comp (ref "R66")
      (value "3.3K")
      (footprint "eagle-import:R0603")
      (libsource (lib "eagle-import") (part "RESISTOR-0603"))
    )
    (comp (ref "U9")
      (value "INA199A2")
      (footprint "eagle-import:SC70-6L")
      (libsource (lib "eagle-import") (part "INA199"))
    )
    (comp (ref "U10")
      (value "INA199A2")
      (footprint "eagle-import:SC70-6L")
      (libsource (lib "eagle-import") (part "INA199"))
    )
    (comp (ref "U11")
      (value "INA199A2")
      (footprint "eagle-import:SC70-6L")
      (libsource (lib "eagle-import") (part "INA199"))
    )
  )
  (nets
    (net (code "1") (name "+3V3") (class "Default")
      (node (ref "C44") (pin "1") (pinfunction "1_1") (pintype "passive"))
      (node (ref "J1") (pin "9") (pinfunction "1_9") (pintype "passive"))
      (node (ref "J4") (pin "13") (pinfunction "1_13") (pintype "passive"))
      (node (ref "J5") (pin "14") (pinfunction "14_14") (pintype "passive"))
      (node (ref "Q8") (pin "1") (pinfunction "G_1") (pintype "passive"))
      (node (ref "Q9") (pin "1") (pinfunction "G_1") (pintype "passive"))
      (node (ref "R24") (pin "1") (pinfunction "1_1") (pintype "passive"))
      (node (ref "R27") (pin "1") (pinfunction "1_1") (pintype "passive"))
      (node (ref "R30") (pin "1") (pinfunction "1_1") (pintype "passive"))
      (node (ref "R33") (pin "1") (pinfunction "1_1") (pintype "passive"))
      (node (ref "R57") (pin "2") (pinfunction "2_2") (pintype "passive"))
      (node (ref "R58") (pin "2") (pinfunction "2_2") (pintype "passive"))
      (node (ref "U12") (pin "5") (pinfunction "VOUT_5") (pintype "bidirectional"))
    )
    (net (code "2") (name "+3V3_HOMEPLUG") (class "Default")
      (node (ref "C16") (pin "1") (pinfunction "1_1") (pintype "passive"))
      (node (ref "J18") (pin "5") (pinfunction "1_5") (pintype "passive"))
      (node (ref "J18") (pin "6") (pinfunction "1_6") (pintype "passive"))
      (node (ref "J9") (pin "2") (pinfunction "S_2") (pintype "passive"))
      (node (ref "LED8") (pin "A") (pinfunction "A_A") (pintype "passive"))
      (node (ref "U5") (pin "2") (pinfunction "VOUT_2") (pintype "bidirectional"))
      (node (ref "U5") (pin "4") (pinfunction "VOUT_4") (pintype "bidirectional"))
    )
    (net (code "3") (name "+5V") (class "Default")
      (node (ref "C13") (pin "1") (pinfunction "1_1") (pintype "passive"))
      (node (ref "C14") (pin "1") (pinfunction "1_1") (pintype "passive"))
      (node (ref "C15") (pin "1") (pinfunction "1_1") (pintype "passive"))
      (node (ref "C17") (pin "1") (pinfunction "1_1") (pintype "passive"))
      (node (ref "C18") (pin "1") (pinfunction "1_1") (pintype "passive"))
      (node (ref "C22") (pin "1") (pinfunction "1_1") (pintype "passive"))
      (node (ref "C23") (pin "1") (pinfunction "1_1") (pintype "passive"))
      (node (ref "C24") (pin "1") (pinfunction "1_1") (pintype "passive"))
      (node (ref "C25") (pin "1") (pinfunction "1_1") (pintype "passive"))
      (node (ref "C3") (pin "1") (pinfunction "1_1") (pintype "passive"))
      (node (ref "C30") (pin "1") (pinfunction "1_1") (pintype "passive"))
      (node (ref "C31") (pin "1") (pinfunction "1_1") (pintype "passive"))
      (node (ref "C32") (pin "1") (pinfunction "1_1") (pintype "passive"))
      (node (ref "C33") (pin "1") (pinfunction "1_1") (pintype "passive"))
      (node (ref "C34") (pin "+") (pinfunction "+_+") (pintype "passive"))
      (node (ref "C4") (pin "1") (pinfunction "1_1") (pintype "passive"))
      (node (ref "C43") (pin "1") (pinfunction "1_1") (pintype "passive"))
      (node (ref "C7") (pin "1") (pinfunction "1_1") (pintype "passive"))
      (node (ref "J1") (pin "10") (pinfunction "1_10") (pintype "passive"))
      (node (ref "J13") (pin "2") (pinfunction "2_2") (pintype "passive"))
      (node (ref "J2") (pin "1") (pinfunction "1_1") (pintype "passive"))
      (node (ref "J2") (pin "15") (pinfunction "1_15") (pintype "passive"))
      (node (ref "J3") (pin "1") (pinfunction "1_1") (pintype "passive"))
      (node (ref "J3") (pin "15") (pinfunction "1_15") (pintype "passive"))
      (node (ref "J4") (pin "15") (pinfunction "1_15") (pintype "passive"))
      (node (ref "J6") (pin "5") (pinfunction "1_5") (pintype "passive"))
      (node (ref "J6") (pin "6") (pinfunction "1_6") (pintype "passive"))
      (node (ref "L1") (pin "2") (pinfunction "2_2") (pintype "passive"))
      (node (ref "LED4") (pin "A") (pinfunction "A_A") (pintype "passive"))
      (node (ref "R15") (pin "2") (pinfunction "2_2") (pintype "passive"))
      (node (ref "R16") (pin "2") (pinfunction "2_2") (pintype "passive"))
      (node (ref "R18") (pin "1") (pinfunction "1_1") (pintype "passive"))
      (node (ref "R20") (pin "1") (pinfunction "1_1") (pintype "passive"))
      (node (ref "R25") (pin "1") (pinfunction "1_1") (pintype "passive"))
      (node (ref "R28") (pin "1") (pinfunction "1_1") (pintype "passive"))
      (node (ref "R31") (pin "1") (pinfunction "1_1") (pintype "passive"))
      (node (ref "R34") (pin "1") (pinfunction "1_1") (pintype "passive"))
      (node (ref "R55") (pin "2") (pinfunction "2_2") (pintype "passive"))
      (node (ref "R56") (pin "2") (pinfunction "2_2") (pintype "passive"))
      (node (ref "SENS1") (pin "3") (pinfunction "V+_3") (pintype "bidirectional"))
      (node (ref "SENS2") (pin "1") (pinfunction "VDD_1") (pintype "bidirectional"))
      (node (ref "U1") (pin "3") (pinfunction "V+_3") (pintype "input"))
      (node (ref "U10") (pin "3") (pinfunction "V+_3") (pintype "input"))
      (node (ref "U11") (pin "3") (pinfunction "V+_3") (pintype "input"))
      (node (ref "U12") (pin "1") (pinfunction "VIN_1") (pintype "bidirectional"))
      (node (ref "U2") (pin "3") (pinfunction "V+_3") (pintype "input"))
      (node (ref "U3") (pin "3") (pinfunction "V+_3") (pintype "input"))
      (node (ref "U5") (pin "3") (pinfunction "VIN_3") (pintype "input"))
      (node (ref "U6") (pin "10") (pinfunction "VCC_10") (pintype "input"))
      (node (ref "U6") (pin "100") (pinfunction "AVCC_100") (pintype "input"))
      (node (ref "U6") (pin "31") (pinfunction "VCC1_31") (pintype "input"))
      (node (ref "U6") (pin "61") (pinfunction "VCC2_61") (pintype "input"))
      (node (ref "U6") (pin "80") (pinfunction "VCC3_80") (pintype "input"))
      (node (ref "U7") (pin "19") (pinfunction "VCCB_19") (pintype "bidirectional"))
      (node (ref "U9") (pin "3") (pinfunction "V+_3") (pintype "input"))
    )
    (net (code "4") (name "3V3_SCL") (class "Default")
      (node (ref "J1") (pin "11") (pinfunction "1_11") (pintype "passive"))
      (node (ref "J5") (pin "15") (pinfunction "15_15") (pintype "passive"))
      (node (ref "Q8") (pin "2") (pinfunction "S_2") (pintype "passive"))
      (node (ref "R57") (pin "1") (pinfunction "1_1") (pintype "passive"))
    )
    (net (code "5") (name "3V3_SDA") (class "Default")
      (node (ref "J1") (pin "13") (pinfunction "1_13") (pintype "passive"))
      (node (ref "J5") (pin "16") (pinfunction "16_16") (pintype "passive"))
      (node (ref "Q9") (pin "2") (pinfunction "S_2") (pintype "passive"))
      (node (ref "R58") (pin "1") (pinfunction "1_1") (pintype "passive"))
    )
    (net (code "6") (name "ADC0") (class "Default")
      (node (ref "C47") (pin "1") (pinfunction "1_1") (pintype "passive"))
      (node (ref "R69") (pin "2") (pinfunction "2_2") (pintype "passive"))
      (node (ref "U6") (pin "97") (pinfunction "(ADC0)PF0_97") (pintype "bidirectional"))
    )
    (net (code "7") (name "ADC1") (class "Default")
      (node (ref "C38") (pin "1") (pinfunction "1_1") (pintype "passive"))
      (node (ref "R66") (pin "2") (pinfunction "2_2") (pintype "passive"))
      (node (ref "U6") (pin "96") (pinfunction "(ADC1)PF1_96") (pintype "bidirectional"))
    )
    (net (code "8") (name "ADC2") (class "Default")
      (node (ref "C37") (pin "1") (pinfunction "1_1") (pintype "passive"))
      (node (ref "R50") (pin "2") (pinfunction "2_2") (pintype "passive"))
      (node (ref "U6") (pin "95") (pinfunction "(ADC2)PF2_95") (pintype "bidirectional"))
    )
    (net (code "9") (name "ADC3") (class "Default")
      (node (ref "C36") (pin "1") (pinfunction "1_1") (pintype "passive"))
      (node (ref "R49") (pin "2") (pinfunction "2_2") (pintype "passive"))
      (node (ref "U6") (pin "94") (pinfunction "(ADC3)PF3_94") (pintype "bidirectional"))
    )
    (net (code "10") (name "ADC4") (class "Default")
      (node (ref "C6") (pin "1") (pinfunction "1_1") (pintype "passive"))
      (node (ref "R10") (pin "2") (pinfunction "2_2") (pintype "passive"))
      (node (ref "R11") (pin "1") (pinfunction "1_1") (pintype "passive"))
      (node (ref "U6") (pin "93") (pinfunction "(ADC4/TCK)PF4_93") (pintype "bidirectional"))
    )
    (net (code "11") (name "ADC5") (class "Default")
      (node (ref "C46") (pin "1") (pinfunction "1_1") (pintype "passive"))
      (node (ref "R68") (pin "2") (pinfunction "2_2") (pintype "passive"))
      (node (ref "U6") (pin "92") (pinfunction "(ADC5/TMS)PF5_92") (pintype "bidirectional"))
    )
    (net (code "12") (name "ADC6") (class "Default")
      (node (ref "C45") (pin "1") (pinfunction "1_1") (pintype "passive"))
      (node (ref "R67") (pin "2") (pinfunction "2_2") (pintype "passive"))
      (node (ref "U6") (pin "91") (pinfunction "(ADC6/TDO)PF6_91") (pintype "bidirectional"))
    )
    (net (code "13") (name "ADC7") (class "Default")
      (node (ref "C27") (pin "1") (pinfunction "1_1") (pintype "passive"))
      (node (ref "R45") (pin "2") (pinfunction "2_2") (pintype "passive"))
      (node (ref "U6") (pin "90") (pinfunction "(ADC7/TDI)PF7_90") (pintype "bidirectional"))
    )
    (net (code "14") (name "ADC8") (class "Default")
      (node (ref "C26") (pin "1") (pinfunction "1_1") (pintype "passive"))
      (node (ref "R44") (pin "2") (pinfunction "2_2") (pintype "passive"))
      (node (ref "U6") (pin "89") (pinfunction "PK0(ADC8/PCINT16)_89") (pintype "bidirectional"))
    )
    (net (code "15") (name "ADC9") (class "Default")
      (node (ref "J4") (pin "14") (pinfunction "1_14") (pintype "passive"))
      (node (ref "U6") (pin "88") (pinfunction "PK1(ADC9/PCINT17)_88") (pintype "bidirectional"))
    )
    (net (code "16") (name "ADC10") (class "Default")
      (node (ref "J4") (pin "12") (pinfunction "1_12") (pintype "passive"))
      (node (ref "U6") (pin "87") (pinfunction "PK2(ADC10/PCINT18)_87") (pintype "bidirectional"))
    )
    (net (code "17") (name "ADC11") (class "Default")
      (node (ref "J4") (pin "10") (pinfunction "1_10") (pintype "passive"))
      (node (ref "U6") (pin "86") (pinfunction "PK3(ADC11/PCINT19)_86") (pintype "bidirectional"))
    )
    (net (code "18") (name "ADC12") (class "Default")
      (node (ref "J4") (pin "8") (pinfunction "1_8") (pintype "passive"))
      (node (ref "U6") (pin "85") (pinfunction "PK4(ADC12/PCINT20)_85") (pintype "bidirectional"))
    )
    (net (code "19") (name "ADC13") (class "Default")
      (node (ref "J4") (pin "6") (pinfunction "1_6") (pintype "passive"))
      (node (ref "U6") (pin "84") (pinfunction "PK5(ADC13/PCINT21)_84") (pintype "bidirectional"))
    )
    (net (code "20") (name "ADC14") (class "Default")
      (node (ref "J4") (pin "4") (pinfunction "1_4") (pintype "passive"))
      (node (ref "U6") (pin "83") (pinfunction "PK6(ADC14/PCINT22)_83") (pintype "bidirectional"))
    )
    (net (code "21") (name "ADC15") (class "Default")
      (node (ref "J4") (pin "2") (pinfunction "1_2") (pintype "passive"))
      (node (ref "U6") (pin "82") (pinfunction "PK7(ADC15/PCINT23)_82") (pintype "bidirectional"))
    )
    (net (code "22") (name "AREF") (class "Default")
      (node (ref "C21") (pin "1") (pinfunction "1_1") (pintype "passive"))
      (node (ref "J4") (pin "16") (pinfunction "1_16") (pintype "passive"))
      (node (ref "U6") (pin "98") (pinfunction "AREF_98") (pintype "bidirectional"))
    )
    (net (code "23") (name "BAT_1+") (class "Default")
      (node (ref "C1") (pin "1") (pinfunction "1_1") (pintype "passive"))
      (node (ref "D1") (pin "1") (pinfunction "A_1") (pintype "passive"))
      (node (ref "D1") (pin "3") (pinfunction "A_3") (pintype "passive"))
      (node (ref "J5") (pin "5") (pinfunction "5_5") (pintype "passive"))
    )
    (net (code "24") (name "BAT_2+") (class "Default")
      (node (ref "C2") (pin "1") (pinfunction "1_1") (pintype "passive"))
      (node (ref "D2") (pin "1") (pinfunction "A_1") (pintype "passive"))
      (node (ref "D2") (pin "3") (pinfunction "A_3") (pintype "passive"))
      (node (ref "J5") (pin "6") (pinfunction "6_6") (pintype "passive"))
    )
    (net (code "25") (name "BB_3V3") (class "Default")
      (node (ref "C28") (pin "1") (pinfunction "1_1") (pintype "passive"))
      (node (ref "C29") (pin "1") (pinfunction "1_1") (pintype "passive"))
      (node (ref "J6") (pin "3") (pinfunction "1_3") (pintype "passive"))
      (node (ref "J6") (pin "4") (pinfunction "1_4") (pintype "passive"))
      (node (ref "LED3") (pin "A") (pinfunction "A_A") (pintype "passive"))
      (node (ref "R46") (pin "2") (pinfunction "2_2") (pintype "passive"))
      (node (ref "R47") (pin "2") (pinfunction "2_2") (pintype "passive"))
      (node (ref "R51") (pin "2") (pinfunction "2_2") (pintype "passive"))
      (node (ref "R52") (pin "2") (pinfunction "2_2") (pintype "passive"))
      (node (ref "R53") (pin "2") (pinfunction "2_2") (pintype "passive"))
      (node (ref "R54") (pin "2") (pinfunction "2_2") (pintype "passive"))
      (node (ref "R62") (pin "2") (pinfunction "2_2") (pintype "passive"))
      (node (ref "R76") (pin "2") (pinfunction "2_2") (pintype "passive"))
      (node (ref "U7") (pin "2") (pinfunction "VCCA_2") (pintype "bidirectional"))
      (node (ref "U8") (pin "8") (pinfunction "VCC_8") (pintype "bidirectional"))
    )
    (net (code "26") (name "BB_P9_11") (class "Default")
      (node (ref "J6") (pin "11") (pinfunction "1_11") (pintype "passive"))
      (node (ref "R46") (pin "1") (pinfunction "1_1") (pintype "passive"))
      (node (ref "U7") (pin "8") (pinfunction "A7_8") (pintype "bidirectional"))
    )
    (net (code "27") (name "BB_P9_12") (class "Default")
      (node (ref "J6") (pin "12") (pinfunction "1_12") (pintype "passive"))
    )
    (net (code "28") (name "BB_P9_13") (class "Default")
      (node (ref "J6") (pin "13") (pinfunction "1_13") (pintype "passive"))
    )
    (net (code "29") (name "BB_P9_14") (class "Default")
      (node (ref "J6") (pin "14") (pinfunction "1_14") (pintype "passive"))
    )
    (net (code "30") (name "BB_P9_15") (class "Default")
      (node (ref "J6") (pin "15") (pinfunction "1_15") (pintype "passive"))
    )
    (net (code "31") (name "BB_P9_16") (class "Default")
      (node (ref "J6") (pin "16") (pinfunction "1_16") (pintype "passive"))
    )
    (net (code "32") (name "BB_P9_17") (class "Default")
      (node (ref "J6") (pin "17") (pinfunction "1_17") (pintype "passive"))
      (node (ref "U7") (pin "4") (pinfunction "A3_4") (pintype "bidirectional"))
    )
    (net (code "33") (name "BB_P9_18") (class "Default")
      (node (ref "J6") (pin "18") (pinfunction "1_18") (pintype "passive"))
      (node (ref "U7") (pin "6") (pinfunction "A5_6") (pintype "bidirectional"))
    )
    (net (code "34") (name "BB_P9_19") (class "Default")
      (node (ref "J6") (pin "19") (pinfunction "1_19") (pintype "passive"))
      (node (ref "R53") (pin "1") (pinfunction "1_1") (pintype "passive"))
      (node (ref "U8") (pin "6") (pinfunction "SCL_6") (pintype "bidirectional"))
    )
    (net (code "35") (name "BB_P9_20") (class "Default")
      (node (ref "J6") (pin "20") (pinfunction "1_20") (pintype "passive"))
      (node (ref "R54") (pin "1") (pinfunction "1_1") (pintype "passive"))
      (node (ref "U8") (pin "5") (pinfunction "SDA_5") (pintype "bidirectional"))
    )
    (net (code "36") (name "BB_P9_21") (class "Default")
      (node (ref "J6") (pin "21") (pinfunction "1_21") (pintype "passive"))
      (node (ref "U7") (pin "7") (pinfunction "A6_7") (pintype "bidirectional"))
    )
    (net (code "37") (name "BB_P9_22") (class "Default")
      (node (ref "J6") (pin "22") (pinfunction "1_22") (pintype "passive"))
      (node (ref "U7") (pin "5") (pinfunction "A4_5") (pintype "bidirectional"))
    )
    (net (code "38") (name "BB_P9_23") (class "Default")
      (node (ref "C48") (pin "1") (pinfunction "1_1") (pintype "passive"))
      (node (ref "J6") (pin "23") (pinfunction "1_23") (pintype "passive"))
      (node (ref "OC2") (pin "4") (pinfunction "C_4") (pintype "passive"))
      (node (ref "R76") (pin "1") (pinfunction "1_1") (pintype "passive"))
    )
    (net (code "39") (name "BB_P9_24") (class "Default")
      (node (ref "J6") (pin "24") (pinfunction "1_24") (pintype "passive"))
      (node (ref "R21") (pin "2") (pinfunction "2_2") (pintype "passive"))
      (node (ref "U7") (pin "1") (pinfunction "A1_1") (pintype "bidirectional"))
    )
    (net (code "40") (name "BB_P9_25") (class "Default")
      (node (ref "J6") (pin "25") (pinfunction "1_25") (pintype "passive"))
    )
    (net (code "41") (name "BB_P9_26") (class "Default")
      (node (ref "J6") (pin "26") (pinfunction "1_26") (pintype "passive"))
      (node (ref "U7") (pin "3") (pinfunction "A2_3") (pintype "bidirectional"))
    )
    (net (code "42") (name "BB_P9_27") (class "Default")
      (node (ref "J6") (pin "27") (pinfunction "1_27") (pintype "passive"))
    )
    (net (code "43") (name "BB_P9_28") (class "Default")
      (node (ref "J6") (pin "28") (pinfunction "1_28") (pintype "passive"))
    )
    (net (code "44") (name "BB_P9_29") (class "Default")
      (node (ref "J6") (pin "29") (pinfunction "1_29") (pintype "passive"))
    )
    (net (code "45") (name "BB_P9_30") (class "Default")
      (node (ref "J6") (pin "30") (pinfunction "1_30") (pintype "passive"))
    )
    (net (code "46") (name "BB_P9_31") (class "Default")
      (node (ref "J6") (pin "31") (pinfunction "1_31") (pintype "passive"))
    )
    (net (code "47") (name "BB_P9_32") (class "Default")
      (node (ref "J6") (pin "32") (pinfunction "1_32") (pintype "passive"))
    )
    (net (code "48") (name "BB_P9_33") (class "Default")
      (node (ref "J6") (pin "33") (pinfunction "1_33") (pintype "passive"))
    )
    (net (code "49") (name "BB_P9_34") (class "Default")
      (node (ref "J6") (pin "34") (pinfunction "1_34") (pintype "passive"))
    )
    (net (code "50") (name "BB_P9_35") (class "Default")
      (node (ref "J6") (pin "35") (pinfunction "1_35") (pintype "passive"))
    )
    (net (code "51") (name "BB_P9_36") (class "Default")
      (node (ref "J6") (pin "36") (pinfunction "1_36") (pintype "passive"))
    )
    (net (code "52") (name "BB_P9_37") (class "Default")
      (node (ref "J6") (pin "37") (pinfunction "1_37") (pintype "passive"))
    )
    (net (code "53") (name "BB_P9_38") (class "Default")
      (node (ref "J6") (pin "38") (pinfunction "1_38") (pintype "passive"))
    )
    (net (code "54") (name "BB_P9_39") (class "Default")
      (node (ref "J6") (pin "39") (pinfunction "1_39") (pintype "passive"))
    )
    (net (code "55") (name "BB_P9_40") (class "Default")
      (node (ref "J6") (pin "40") (pinfunction "1_40") (pintype "passive"))
    )
    (net (code "56") (name "BB_P9_41") (class "Default")
      (node (ref "J6") (pin "41") (pinfunction "1_41") (pintype "passive"))
    )
    (net (code "57") (name "BB_P9_42") (class "Default")
      (node (ref "J6") (pin "42") (pinfunction "1_42") (pintype "passive"))
    )
    (net (code "58") (name "BB_PWR_BUT") (class "Default")
      (node (ref "J6") (pin "9") (pinfunction "1_9") (pintype "passive"))
    )
    (net (code "59") (name "BB_SYS_5V") (class "Default")
      (node (ref "J6") (pin "7") (pinfunction "1_7") (pintype "passive"))
      (node (ref "J6") (pin "8") (pinfunction "1_8") (pintype "passive"))
    )
    (net (code "60") (name "BB_SYS_RESET*") (class "Default")
      (node (ref "J6") (pin "10") (pinfunction "1_10") (pintype "passive"))
      (node (ref "R48") (pin "2") (pinfunction "2_2") (pintype "passive"))
    )
    (net (code "61") (name "D0{slash}UART_RX") (class "Default")
      (node (ref "U6") (pin "2") (pinfunction "(RXD0/PCIN8)PE0_2") (pintype "bidirectional"))
      (node (ref "U7") (pin "20") (pinfunction "B1_20") (pintype "bidirectional"))
    )
    (net (code "62") (name "D1{slash}UART_TX") (class "Default")
      (node (ref "R22") (pin "2") (pinfunction "2_2") (pintype "passive"))
      (node (ref "U6") (pin "3") (pinfunction "(TXD0)PE1_3") (pintype "bidirectional"))
      (node (ref "U7") (pin "18") (pinfunction "B2_18") (pintype "bidirectional"))
    )
    (net (code "63") (name "D2") (class "Default")
      (node (ref "J3") (pin "11") (pinfunction "1_11") (pintype "passive"))
      (node (ref "U6") (pin "6") (pinfunction "(OC3B/INT4)PE4_6") (pintype "bidirectional"))
    )
    (net (code "64") (name "D3") (class "Default")
      (node (ref "J3") (pin "9") (pinfunction "1_9") (pintype "passive"))
      (node (ref "U6") (pin "7") (pinfunction "(OC3C/INT5)PE5_7") (pintype "bidirectional"))
    )
    (net (code "65") (name "D4") (class "Default")
      (node (ref "J3") (pin "7") (pinfunction "1_7") (pintype "passive"))
      (node (ref "U6") (pin "1") (pinfunction "(OC0B)PG5_1") (pintype "bidirectional"))
    )
    (net (code "66") (name "D5") (class "Default")
      (node (ref "J3") (pin "5") (pinfunction "1_5") (pintype "passive"))
      (node (ref "U6") (pin "5") (pinfunction "(OC3A/AIN1)PE3_5") (pintype "bidirectional"))
    )
    (net (code "67") (name "D6") (class "Default")
      (node (ref "J20") (pin "P1") (pinfunction "1_P1") (pintype "passive"))
      (node (ref "U6") (pin "15") (pinfunction "PH3(OC4A)_15") (pintype "bidirectional"))
    )
    (net (code "68") (name "D7") (class "Default")
      (node (ref "J20") (pin "P4") (pinfunction "1_P4") (pintype "passive"))
      (node (ref "U6") (pin "16") (pinfunction "PH4(OC4B)_16") (pintype "bidirectional"))
    )
    (net (code "69") (name "D8") (class "Default")
      (node (ref "J20") (pin "P7") (pinfunction "1_P7") (pintype "passive"))
      (node (ref "U6") (pin "17") (pinfunction "PH5(OC4C)_17") (pintype "bidirectional"))
    )
    (net (code "70") (name "D9") (class "Default")
      (node (ref "J21") (pin "P1") (pinfunction "1_P1") (pintype "passive"))
      (node (ref "R70") (pin "1") (pinfunction "1_1") (pintype "passive"))
      (node (ref "U6") (pin "18") (pinfunction "PH6(OC2B)_18") (pintype "bidirectional"))
    )
    (net (code "71") (name "D10") (class "Default")
      (node (ref "J21") (pin "P4") (pinfunction "1_P4") (pintype "passive"))
      (node (ref "U6") (pin "23") (pinfunction "(OC2A/PCINT4)PB4_23") (pintype "bidirectional"))
    )
    (net (code "72") (name "D11") (class "Default")
      (node (ref "J21") (pin "P7") (pinfunction "1_P7") (pintype "passive"))
      (node (ref "U6") (pin "24") (pinfunction "(OC1A/PCINT5)PB5_24") (pintype "bidirectional"))
    )
    (net (code "73") (name "D12") (class "Default")
      (node (ref "R39") (pin "1") (pinfunction "1_1") (pintype "passive"))
      (node (ref "U6") (pin "25") (pinfunction "(OC1B/PCINT6)PB6_25") (pintype "bidirectional"))
    )
    (net (code "74") (name "D13") (class "Default")
      (node (ref "R23") (pin "1") (pinfunction "1_1") (pintype "passive"))
      (node (ref "U6") (pin "26") (pinfunction "(OC0A/OC1C/PCINT7)PB7_26") (pintype "bidirectional"))
    )
    (net (code "75") (name "D14") (class "Default")
      (node (ref "J2") (pin "11") (pinfunction "1_11") (pintype "passive"))
      (node (ref "U6") (pin "64") (pinfunction "PJ1(TXD3/PCINT10)_64") (pintype "bidirectional"))
    )
    (net (code "76") (name "D15") (class "Default")
      (node (ref "J2") (pin "9") (pinfunction "1_9") (pintype "passive"))
      (node (ref "U6") (pin "63") (pinfunction "PJ0(RXD3/PCINT9)_63") (pintype "bidirectional"))
    )
    (net (code "77") (name "D16{slash}ESC_POWER_SWITCH") (class "Default")
      (node (ref "R5") (pin "2") (pinfunction "2_2") (pintype "passive"))
      (node (ref "U6") (pin "13") (pinfunction "PH1(TXD2)_13") (pintype "bidirectional"))
    )
    (net (code "78") (name "D17") (class "Default")
      (node (ref "U6") (pin "12") (pinfunction "PH0(RXD2)_12") (pintype "bidirectional"))
    )
    (net (code "79") (name "D18") (class "Default")
      (node (ref "J2") (pin "7") (pinfunction "1_7") (pintype "passive"))
      (node (ref "U6") (pin "46") (pinfunction "(TXD1/INT3)PD3_46") (pintype "bidirectional"))
    )
    (net (code "80") (name "D19") (class "Default")
      (node (ref "J2") (pin "5") (pinfunction "1_5") (pintype "passive"))
      (node (ref "U6") (pin "45") (pinfunction "(RXD1/INT2)PD2_45") (pintype "bidirectional"))
    )
    (net (code "81") (name "D20{slash}5V_SDA") (class "Default")
      (node (ref "J1") (pin "14") (pinfunction "1_14") (pintype "passive"))
      (node (ref "Q9") (pin "3") (pinfunction "D_3") (pintype "passive"))
      (node (ref "R56") (pin "1") (pinfunction "1_1") (pintype "passive"))
      (node (ref "U6") (pin "44") (pinfunction "(SDA/INT1)PD1_44") (pintype "bidirectional"))
    )
    (net (code "82") (name "D21{slash}5V_SCL") (class "Default")
      (node (ref "J1") (pin "12") (pinfunction "1_12") (pintype "passive"))
      (node (ref "Q8") (pin "3") (pinfunction "D_3") (pintype "passive"))
      (node (ref "R55") (pin "1") (pinfunction "1_1") (pintype "passive"))
      (node (ref "U6") (pin "43") (pinfunction "(SCL/INT0)PD0_43") (pintype "bidirectional"))
    )
    (net (code "83") (name "D22") (class "Default")
      (node (ref "J3") (pin "16") (pinfunction "1_16") (pintype "passive"))
      (node (ref "U6") (pin "78") (pinfunction "(AD0)PA0_78") (pintype "bidirectional"))
    )
    (net (code "84") (name "D23") (class "Default")
      (node (ref "J3") (pin "14") (pinfunction "1_14") (pintype "passive"))
      (node (ref "U6") (pin "77") (pinfunction "(AD1)PA1_77") (pintype "bidirectional"))
    )
    (net (code "85") (name "D24") (class "Default")
      (node (ref "J3") (pin "12") (pinfunction "1_12") (pintype "passive"))
      (node (ref "U6") (pin "76") (pinfunction "(AD2)PA2_76") (pintype "bidirectional"))
    )
    (net (code "86") (name "D25") (class "Default")
      (node (ref "J3") (pin "10") (pinfunction "1_10") (pintype "passive"))
      (node (ref "U6") (pin "75") (pinfunction "(AD3)PA3_75") (pintype "bidirectional"))
    )
    (net (code "87") (name "D26") (class "Default")
      (node (ref "J3") (pin "8") (pinfunction "1_8") (pintype "passive"))
      (node (ref "U6") (pin "74") (pinfunction "(AD4)PA4_74") (pintype "bidirectional"))
    )
    (net (code "88") (name "D27") (class "Default")
      (node (ref "J3") (pin "6") (pinfunction "1_6") (pintype "passive"))
      (node (ref "U6") (pin "73") (pinfunction "(AD5)PA5_73") (pintype "bidirectional"))
    )
    (net (code "89") (name "D28") (class "Default")
      (node (ref "J3") (pin "4") (pinfunction "1_4") (pintype "passive"))
      (node (ref "U6") (pin "72") (pinfunction "(AD6)PA6_72") (pintype "bidirectional"))
    )
    (net (code "90") (name "D29") (class "Default")
      (node (ref "J3") (pin "2") (pinfunction "1_2") (pintype "passive"))
      (node (ref "U6") (pin "71") (pinfunction "(AD7)PA7_71") (pintype "bidirectional"))
    )
    (net (code "91") (name "D30") (class "Default")
      (node (ref "J2") (pin "16") (pinfunction "1_16") (pintype "passive"))
      (node (ref "U6") (pin "60") (pinfunction "(A15)PC7_60") (pintype "bidirectional"))
    )
    (net (code "92") (name "D31") (class "Default")
      (node (ref "J2") (pin "14") (pinfunction "1_14") (pintype "passive"))
      (node (ref "U6") (pin "59") (pinfunction "(A14)PC6_59") (pintype "bidirectional"))
    )
    (net (code "93") (name "D32") (class "Default")
      (node (ref "J2") (pin "12") (pinfunction "1_12") (pintype "passive"))
      (node (ref "U6") (pin "58") (pinfunction "(A13)PC5_58") (pintype "bidirectional"))
    )
    (net (code "94") (name "D33") (class "Default")
      (node (ref "J2") (pin "10") (pinfunction "1_10") (pintype "passive"))
      (node (ref "U6") (pin "57") (pinfunction "(A12)PC4_57") (pintype "bidirectional"))
    )
    (net (code "95") (name "D34") (class "Default")
      (node (ref "J2") (pin "8") (pinfunction "1_8") (pintype "passive"))
      (node (ref "U6") (pin "56") (pinfunction "(A11)PC3_56") (pintype "bidirectional"))
    )
    (net (code "96") (name "D35") (class "Default")
      (node (ref "J2") (pin "6") (pinfunction "1_6") (pintype "passive"))
      (node (ref "U6") (pin "55") (pinfunction "(A10)PC2_55") (pintype "bidirectional"))
    )
    (net (code "97") (name "D36") (class "Default")
      (node (ref "J2") (pin "4") (pinfunction "1_4") (pintype "passive"))
      (node (ref "U6") (pin "54") (pinfunction "(A9)PC1_54") (pintype "bidirectional"))
    )
    (net (code "98") (name "D37") (class "Default")
      (node (ref "J2") (pin "2") (pinfunction "1_2") (pintype "passive"))
      (node (ref "U6") (pin "53") (pinfunction "(A8)PC0_53") (pintype "bidirectional"))
    )
    (net (code "99") (name "D38") (class "Default")
      (node (ref "U6") (pin "50") (pinfunction "(T0)PD7_50") (pintype "bidirectional"))
    )
    (net (code "100") (name "D39") (class "Default")
      (node (ref "U6") (pin "70") (pinfunction "(ALE)PG2_70") (pintype "bidirectional"))
    )
    (net (code "101") (name "D40") (class "Default")
      (node (ref "U6") (pin "52") (pinfunction "(RD)PG1_52") (pintype "bidirectional"))
    )
    (net (code "102") (name "D41") (class "Default")
      (node (ref "U6") (pin "51") (pinfunction "(WR)PG0_51") (pintype "bidirectional"))
    )
    (net (code "103") (name "D42") (class "Default")
      (node (ref "U6") (pin "42") (pinfunction "PL7_42") (pintype "bidirectional"))
    )
    (net (code "104") (name "D43") (class "Default")
      (node (ref "U6") (pin "41") (pinfunction "PL6_41") (pintype "bidirectional"))
    )
    (net (code "105") (name "D44") (class "Default")
      (node (ref "R36") (pin "1") (pinfunction "1_1") (pintype "passive"))
      (node (ref "U6") (pin "40") (pinfunction "PL5(OC5C)_40") (pintype "bidirectional"))
    )
    (net (code "106") (name "D45") (class "Default")
      (node (ref "R37") (pin "1") (pinfunction "1_1") (pintype "passive"))
      (node (ref "U6") (pin "39") (pinfunction "PL4(OC5B)_39") (pintype "bidirectional"))
    )
    (net (code "107") (name "D46") (class "Default")
      (node (ref "R38") (pin "1") (pinfunction "1_1") (pintype "passive"))
      (node (ref "U6") (pin "38") (pinfunction "PL3(OC5A)_38") (pintype "bidirectional"))
    )
    (net (code "108") (name "D47") (class "Default")
      (node (ref "U6") (pin "37") (pinfunction "PL2(T5)_37") (pintype "bidirectional"))
    )
    (net (code "109") (name "D48{slash}3.3V_ENABLE") (class "Default")
      (node (ref "R15") (pin "1") (pinfunction "1_1") (pintype "passive"))
      (node (ref "U12") (pin "3") (pinfunction "CTRL_3") (pintype "bidirectional"))
      (node (ref "U6") (pin "36") (pinfunction "PL1(ICP5)_36") (pintype "bidirectional"))
    )
    (net (code "110") (name "D49") (class "Default")
      (node (ref "R19") (pin "1") (pinfunction "1_1") (pintype "passive"))
      (node (ref "U6") (pin "35") (pinfunction "PL0(ICP4)_35") (pintype "bidirectional"))
    )
    (net (code "111") (name "D50{slash}SPI_MISO") (class "Default")
      (node (ref "J13") (pin "1") (pinfunction "1_1") (pintype "passive"))
      (node (ref "U6") (pin "22") (pinfunction "(MISO/PCINT3)PB3_22") (pintype "bidirectional"))
      (node (ref "U7") (pin "14") (pinfunction "B6_14") (pintype "bidirectional"))
    )
    (net (code "112") (name "D51{slash}SPI_MOSI") (class "Default")
      (node (ref "J13") (pin "4") (pinfunction "4_4") (pintype "passive"))
      (node (ref "U6") (pin "21") (pinfunction "(MOSI/PCINT2)PB2_21") (pintype "bidirectional"))
      (node (ref "U7") (pin "15") (pinfunction "B5_15") (pintype "bidirectional"))
    )
    (net (code "113") (name "D52{slash}SPI_SCK") (class "Default")
      (node (ref "J13") (pin "3") (pinfunction "3_3") (pintype "passive"))
      (node (ref "U6") (pin "20") (pinfunction "(SCK/PCINT1)PB1_20") (pintype "bidirectional"))
      (node (ref "U7") (pin "16") (pinfunction "B4_16") (pintype "bidirectional"))
    )
    (net (code "114") (name "D53{slash}SPI_SS") (class "Default")
      (node (ref "U6") (pin "19") (pinfunction "(SS/PCINT0)PB0_19") (pintype "bidirectional"))
      (node (ref "U7") (pin "17") (pinfunction "B3_17") (pintype "bidirectional"))
    )
    (net (code "115") (name "ESC_1A") (class "Default")
      (node (ref "J14") (pin "A1") (pinfunction "S_A1") (pintype "passive"))
      (node (ref "J14") (pin "A2") (pinfunction "S_A2") (pintype "passive"))
      (node (ref "J5") (pin "1") (pinfunction "1_1") (pintype "passive"))
    )
    (net (code "116") (name "ESC_1B") (class "Default")
      (node (ref "J14") (pin "B1") (pinfunction "S_B1") (pintype "passive"))
      (node (ref "J14") (pin "B2") (pinfunction "S_B2") (pintype "passive"))
      (node (ref "J5") (pin "2") (pinfunction "2_2") (pintype "passive"))
    )
    (net (code "117") (name "ESC_1C") (class "Default")
      (node (ref "J14") (pin "C1") (pinfunction "S_C1") (pintype "passive"))
      (node (ref "J14") (pin "C2") (pinfunction "S_C2") (pintype "passive"))
      (node (ref "J5") (pin "3") (pinfunction "3_3") (pintype "passive"))
    )
    (net (code "118") (name "ESC_2A") (class "Default")
      (node (ref "J15") (pin "A1") (pinfunction "S_A1") (pintype "passive"))
      (node (ref "J15") (pin "A2") (pinfunction "S_A2") (pintype "passive"))
      (node (ref "J5") (pin "8") (pinfunction "8_8") (pintype "passive"))
    )
    (net (code "119") (name "ESC_2B") (class "Default")
      (node (ref "J15") (pin "B1") (pinfunction "S_B1") (pintype "passive"))
      (node (ref "J15") (pin "B2") (pinfunction "S_B2") (pintype "passive"))
      (node (ref "J5") (pin "9") (pinfunction "9_9") (pintype "passive"))
    )
    (net (code "120") (name "ESC_2C") (class "Default")
      (node (ref "J15") (pin "C1") (pinfunction "S_C1") (pintype "passive"))
      (node (ref "J15") (pin "C2") (pinfunction "S_C2") (pintype "passive"))
      (node (ref "J5") (pin "10") (pinfunction "10_10") (pintype "passive"))
    )
    (net (code "121") (name "ESC_3A") (class "Default")
      (node (ref "J16") (pin "A1") (pinfunction "S_A1") (pintype "passive"))
      (node (ref "J16") (pin "A2") (pinfunction "S_A2") (pintype "passive"))
      (node (ref "J5") (pin "11") (pinfunction "11_11") (pintype "passive"))
    )
    (net (code "122") (name "ESC_3B") (class "Default")
      (node (ref "J16") (pin "B1") (pinfunction "S_B1") (pintype "passive"))
      (node (ref "J16") (pin "B2") (pinfunction "S_B2") (pintype "passive"))
      (node (ref "J5") (pin "12") (pinfunction "12_12") (pintype "passive"))
    )
    (net (code "123") (name "ESC_3C") (class "Default")
      (node (ref "J16") (pin "C1") (pinfunction "S_C1") (pintype "passive"))
      (node (ref "J16") (pin "C2") (pinfunction "S_C2") (pintype "passive"))
      (node (ref "J5") (pin "13") (pinfunction "13_13") (pintype "passive"))
    )
    (net (code "124") (name "ESC_POWER") (class "Default")
      (node (ref "Q3") (pin "5") (pinfunction "D_5") (pintype "passive"))
      (node (ref "Q3") (pin "6") (pinfunction "D_6") (pintype "passive"))
      (node (ref "Q3") (pin "7") (pinfunction "D_7") (pintype "passive"))
      (node (ref "Q3") (pin "8") (pinfunction "D_8") (pintype "passive"))
      (node (ref "R59") (pin "1") (pinfunction "1_1") (pintype "passive"))
      (node (ref "R60") (pin "1") (pinfunction "1_1") (pintype "passive"))
      (node (ref "R61") (pin "1") (pinfunction "1_1") (pintype "passive"))
      (node (ref "U10") (pin "4") (pinfunction "IN+_4") (pintype "input"))
      (node (ref "U11") (pin "4") (pinfunction "IN+_4") (pintype "input"))
      (node (ref "U9") (pin "4") (pinfunction "IN+_4") (pintype "input"))
    )
    (net (code "125") (name "GND") (class "Default")
      (node (ref "C1") (pin "2") (pinfunction "2_2") (pintype "passive"))
      (node (ref "C11") (pin "2") (pinfunction "2_2") (pintype "passive"))
      (node (ref "C13") (pin "2") (pinfunction "2_2") (pintype "passive"))
      (node (ref "C14") (pin "2") (pinfunction "2_2") (pintype "passive"))
      (node (ref "C15") (pin "2") (pinfunction "2_2") (pintype "passive"))
      (node (ref "C16") (pin "2") (pinfunction "2_2") (pintype "passive"))
      (node (ref "C17") (pin "2") (pinfunction "2_2") (pintype "passive"))
      (node (ref "C18") (pin "2") (pinfunction "2_2") (pintype "passive"))
      (node (ref "C19") (pin "2") (pinfunction "2_2") (pintype "passive"))
      (node (ref "C2") (pin "2") (pinfunction "2_2") (pintype "passive"))
      (node (ref "C20") (pin "2") (pinfunction "2_2") (pintype "passive"))
      (node (ref "C21") (pin "2") (pinfunction "2_2") (pintype "passive"))
      (node (ref "C22") (pin "2") (pinfunction "2_2") (pintype "passive"))
      (node (ref "C23") (pin "2") (pinfunction "2_2") (pintype "passive"))
      (node (ref "C24") (pin "2") (pinfunction "2_2") (pintype "passive"))
      (node (ref "C25") (pin "2") (pinfunction "2_2") (pintype "passive"))
      (node (ref "C26") (pin "2") (pinfunction "2_2") (pintype "passive"))
      (node (ref "C27") (pin "2") (pinfunction "2_2") (pintype "passive"))
      (node (ref "C28") (pin "2") (pinfunction "2_2") (pintype "passive"))
      (node (ref "C29") (pin "2") (pinfunction "2_2") (pintype "passive"))
      (node (ref "C3") (pin "2") (pinfunction "2_2") (pintype "passive"))
      (node (ref "C30") (pin "2") (pinfunction "2_2") (pintype "passive"))
      (node (ref "C31") (pin "2") (pinfunction "2_2") (pintype "passive"))
      (node (ref "C32") (pin "2") (pinfunction "2_2") (pintype "passive"))
      (node (ref "C33") (pin "2") (pinfunction "2_2") (pintype "passive"))
      (node (ref "C34") (pin "-") (pinfunction "-_-") (pintype "passive"))
      (node (ref "C35") (pin "2") (pinfunction "2_2") (pintype "passive"))
      (node (ref "C36") (pin "2") (pinfunction "2_2") (pintype "passive"))
      (node (ref "C37") (pin "2") (pinfunction "2_2") (pintype "passive"))
      (node (ref "C38") (pin "2") (pinfunction "2_2") (pintype "passive"))
      (node (ref "C39") (pin "-") (pinfunction "-_-") (pintype "passive"))
      (node (ref "C4") (pin "2") (pinfunction "2_2") (pintype "passive"))
      (node (ref "C40") (pin "-") (pinfunction "-_-") (pintype "passive"))
      (node (ref "C41") (pin "-") (pinfunction "-_-") (pintype "passive"))
      (node (ref "C43") (pin "2") (pinfunction "2_2") (pintype "passive"))
      (node (ref "C44") (pin "2") (pinfunction "2_2") (pintype "passive"))
      (node (ref "C45") (pin "2") (pinfunction "2_2") (pintype "passive"))
      (node (ref "C46") (pin "2") (pinfunction "2_2") (pintype "passive"))
      (node (ref "C47") (pin "2") (pinfunction "2_2") (pintype "passive"))
      (node (ref "C48") (pin "2") (pinfunction "2_2") (pintype "passive"))
      (node (ref "C6") (pin "2") (pinfunction "2_2") (pintype "passive"))
      (node (ref "C7") (pin "2") (pinfunction "2_2") (pintype "passive"))
      (node (ref "C8") (pin "2") (pinfunction "2_2") (pintype "passive"))
      (node (ref "C9") (pin "2") (pinfunction "2_2") (pintype "passive"))
      (node (ref "D3") (pin "A") (pinfunction "A_A") (pintype "passive"))
      (node (ref "D6") (pin "A") (pinfunction "A_A") (pintype "passive"))
      (node (ref "J1") (pin "15") (pinfunction "1_15") (pintype "passive"))
      (node (ref "J1") (pin "16") (pinfunction "1_16") (pintype "passive"))
      (node (ref "J11") (pin "2") (pinfunction "S_2") (pintype "passive"))
      (node (ref "J12") (pin "2") (pinfunction "S_2") (pintype "passive"))
      (node (ref "J13") (pin "6") (pinfunction "6_6") (pintype "passive"))
      (node (ref "J14") (pin "GND1") (pinfunction "S_GND1") (pintype "passive"))
      (node (ref "J14") (pin "GND2") (pinfunction "S_GND2") (pintype "passive"))
      (node (ref "J15") (pin "GND1") (pinfunction "S_GND1") (pintype "passive"))
      (node (ref "J15") (pin "GND2") (pinfunction "S_GND2") (pintype "passive"))
      (node (ref "J16") (pin "GND1") (pinfunction "S_GND1") (pintype "passive"))
      (node (ref "J16") (pin "GND2") (pinfunction "S_GND2") (pintype "passive"))
      (node (ref "J17") (pin "2") (pinfunction "S_2") (pintype "passive"))
      (node (ref "J18") (pin "1") (pinfunction "1_1") (pintype "passive"))
      (node (ref "J2") (pin "13") (pinfunction "1_13") (pintype "passive"))
      (node (ref "J2") (pin "3") (pinfunction "1_3") (pintype "passive"))
      (node (ref "J20") (pin "P3") (pinfunction "1_P3") (pintype "passive"))
      (node (ref "J20") (pin "P6") (pinfunction "1_P6") (pintype "passive"))
      (node (ref "J20") (pin "P9") (pinfunction "1_P9") (pintype "passive"))
      (node (ref "J21") (pin "P3") (pinfunction "1_P3") (pintype "passive"))
      (node (ref "J21") (pin "P6") (pinfunction "1_P6") (pintype "passive"))
      (node (ref "J21") (pin "P9") (pinfunction "1_P9") (pintype "passive"))
      (node (ref "J3") (pin "13") (pinfunction "1_13") (pintype "passive"))
      (node (ref "J3") (pin "3") (pinfunction "1_3") (pintype "passive"))
      (node (ref "J4") (pin "1") (pinfunction "1_1") (pintype "passive"))
      (node (ref "J4") (pin "11") (pinfunction "1_11") (pintype "passive"))
      (node (ref "J4") (pin "3") (pinfunction "1_3") (pintype "passive"))
      (node (ref "J4") (pin "5") (pinfunction "1_5") (pintype "passive"))
      (node (ref "J4") (pin "7") (pinfunction "1_7") (pintype "passive"))
      (node (ref "J4") (pin "9") (pinfunction "1_9") (pintype "passive"))
      (node (ref "J5") (pin "17") (pinfunction "17_17") (pintype "passive"))
      (node (ref "J5") (pin "4") (pinfunction "4_4") (pintype "passive"))
      (node (ref "J5") (pin "7") (pinfunction "7_7") (pintype "passive"))
      (node (ref "J6") (pin "1") (pinfunction "1_1") (pintype "passive"))
      (node (ref "J6") (pin "2") (pinfunction "1_2") (pintype "passive"))
      (node (ref "J6") (pin "43") (pinfunction "1_43") (pintype "passive"))
      (node (ref "J6") (pin "44") (pinfunction "1_44") (pintype "passive"))
      (node (ref "J6") (pin "45") (pinfunction "1_45") (pintype "passive"))
      (node (ref "J6") (pin "46") (pinfunction "1_46") (pintype "passive"))
      (node (ref "J7") (pin "2") (pinfunction "S_2") (pintype "passive"))
      (node (ref "J9") (pin "1") (pinfunction "S_1") (pintype "passive"))
      (node (ref "J9") (pin "3") (pinfunction "S_3") (pintype "passive"))
      (node (ref "LED1") (pin "C") (pinfunction "C_C") (pintype "passive"))
      (node (ref "LED2") (pin "C") (pinfunction "C_C") (pintype "passive"))
      (node (ref "LED5") (pin "C") (pinfunction "C_C") (pintype "passive"))
      (node (ref "LED6") (pin "C") (pinfunction "C_C") (pintype "passive"))
      (node (ref "LED7") (pin "C") (pinfunction "C_C") (pintype "passive"))
      (node (ref "OC1") (pin "3") (pinfunction "E_3") (pintype "passive"))
      (node (ref "OC2") (pin "3") (pinfunction "E_3") (pintype "passive"))
      (node (ref "Q2") (pin "2") (pinfunction "S_2") (pintype "passive"))
      (node (ref "Q4") (pin "2") (pinfunction "S_2") (pintype "passive"))
      (node (ref "Q5") (pin "2") (pinfunction "S_2") (pintype "passive"))
      (node (ref "Q6") (pin "2") (pinfunction "S_2") (pintype "passive"))
      (node (ref "Q7") (pin "2") (pinfunction "S_2") (pintype "passive"))
      (node (ref "R11") (pin "2") (pinfunction "2_2") (pintype "passive"))
      (node (ref "R14") (pin "1") (pinfunction "1_1") (pintype "passive"))
      (node (ref "R17") (pin "1") (pinfunction "1_1") (pintype "passive"))
      (node (ref "R40") (pin "1") (pinfunction "1_1") (pintype "passive"))
      (node (ref "R41") (pin "1") (pinfunction "1_1") (pintype "passive"))
      (node (ref "R42") (pin "1") (pinfunction "1_1") (pintype "passive"))
      (node (ref "R43") (pin "1") (pinfunction "1_1") (pintype "passive"))
      (node (ref "R7") (pin "2") (pinfunction "2_2") (pintype "passive"))
      (node (ref "R72") (pin "1") (pinfunction "1_1") (pintype "passive"))
      (node (ref "SENS1") (pin "1") (pinfunction "GND_1") (pintype "bidirectional"))
      (node (ref "SENS2") (pin "3") (pinfunction "GND_3") (pintype "bidirectional"))
      (node (ref "TP2") (pin "1") (pinfunction "P_1") (pintype "passive"))
      (node (ref "TP3") (pin "1") (pinfunction "P_1") (pintype "passive"))
      (node (ref "U1") (pin "1") (pinfunction "REF_1") (pintype "input"))
      (node (ref "U1") (pin "2") (pinfunction "GND_2") (pintype "input"))
      (node (ref "U10") (pin "1") (pinfunction "REF_1") (pintype "input"))
      (node (ref "U10") (pin "2") (pinfunction "GND_2") (pintype "input"))
      (node (ref "U11") (pin "1") (pinfunction "REF_1") (pintype "input"))
      (node (ref "U11") (pin "2") (pinfunction "GND_2") (pintype "input"))
      (node (ref "U12") (pin "2") (pinfunction "GND_2") (pintype "bidirectional"))
      (node (ref "U2") (pin "1") (pinfunction "REF_1") (pintype "input"))
      (node (ref "U2") (pin "2") (pinfunction "GND_2") (pintype "input"))
      (node (ref "U3") (pin "1") (pinfunction "REF_1") (pintype "input"))
      (node (ref "U3") (pin "2") (pinfunction "GND_2") (pintype "input"))
      (node (ref "U4") (pin "4") (pinfunction "GND_4") (pintype "bidirectional"))
      (node (ref "U4") (pin "PAD") (pinfunction "GNDPAD_PAD") (pintype "bidirectional"))
      (node (ref "U5") (pin "1") (pinfunction "GND_1") (pintype "power_in"))
      (node (ref "U6") (pin "11") (pinfunction "GND_11") (pintype "input"))
      (node (ref "U6") (pin "32") (pinfunction "GND1_32") (pintype "input"))
      (node (ref "U6") (pin "62") (pinfunction "GND2_62") (pintype "input"))
      (node (ref "U6") (pin "81") (pinfunction "GND3_81") (pintype "input"))
      (node (ref "U6") (pin "99") (pinfunction "AGND_99") (pintype "input"))
      (node (ref "U7") (pin "11") (pinfunction "GND_11") (pintype "bidirectional"))
      (node (ref "U8") (pin "1") (pinfunction "A0_1") (pintype "input"))
      (node (ref "U8") (pin "2") (pinfunction "A1_2") (pintype "input"))
      (node (ref "U8") (pin "4") (pinfunction "VSS_4") (pintype "bidirectional"))
      (node (ref "U9") (pin "1") (pinfunction "REF_1") (pintype "input"))
      (node (ref "U9") (pin "2") (pinfunction "GND_2") (pintype "input"))
    )
    (net (code "126") (name "Net-(C5-Pad1)") (class "Default")
      (node (ref "C5") (pin "1") (pinfunction "1_1") (pintype "passive"))
      (node (ref "FB1") (pin "2") (pinfunction "2_2") (pintype "passive"))
      (node (ref "R3") (pin "2") (pinfunction "2_2") (pintype "passive"))
      (node (ref "R75") (pin "2") (pinfunction "2_2") (pintype "passive"))
    )
    (net (code "127") (name "Net-(C10-Pad2)") (class "Default")
      (node (ref "C10") (pin "2") (pinfunction "2_2") (pintype "passive"))
      (node (ref "R14") (pin "2") (pinfunction "2_2") (pintype "passive"))
    )
    (net (code "128") (name "Net-(D1-C)") (class "Default")
      (node (ref "D1") (pin "4") (pinfunction "C_4") (pintype "passive"))
      (node (ref "R1") (pin "1") (pinfunction "1_1") (pintype "passive"))
      (node (ref "U2") (pin "4") (pinfunction "IN+_4") (pintype "input"))
    )
    (net (code "129") (name "Net-(D2-C)") (class "Default")
      (node (ref "D2") (pin "4") (pinfunction "C_4") (pintype "passive"))
      (node (ref "R2") (pin "1") (pinfunction "1_1") (pintype "passive"))
      (node (ref "U1") (pin "4") (pinfunction "IN+_4") (pintype "input"))
    )
    (net (code "130") (name "Net-(J11A-S)") (class "Default")
      (node (ref "C42") (pin "1") (pinfunction "1_1") (pintype "passive"))
      (node (ref "D3") (pin "C") (pinfunction "C_C") (pintype "passive"))
      (node (ref "D4") (pin "C") (pinfunction "C_C") (pintype "passive"))
      (node (ref "D5") (pin "C") (pinfunction "C_C") (pintype "passive"))
      (node (ref "J11") (pin "1") (pinfunction "S_1") (pintype "passive"))
      (node (ref "Q1") (pin "1") (pinfunction "S_1") (pintype "passive"))
      (node (ref "Q1") (pin "2") (pinfunction "S_2") (pintype "passive"))
      (node (ref "Q1") (pin "3") (pinfunction "S_3") (pintype "passive"))
      (node (ref "Q3") (pin "1") (pinfunction "S_1") (pintype "passive"))
      (node (ref "Q3") (pin "2") (pinfunction "S_2") (pintype "passive"))
      (node (ref "Q3") (pin "3") (pinfunction "S_3") (pintype "passive"))
      (node (ref "R1") (pin "2") (pinfunction "2_2") (pintype "passive"))
      (node (ref "R2") (pin "2") (pinfunction "2_2") (pintype "passive"))
      (node (ref "R4") (pin "2") (pinfunction "2_2") (pintype "passive"))
      (node (ref "R6") (pin "2") (pinfunction "2_2") (pintype "passive"))
      (node (ref "U1") (pin "5") (pinfunction "IN-_5") (pintype "input"))
      (node (ref "U2") (pin "5") (pinfunction "IN-_5") (pintype "input"))
    )
    (net (code "131") (name "Net-(J12A-S)") (class "Default")
      (node (ref "C35") (pin "1") (pinfunction "1_1") (pintype "passive"))
      (node (ref "J12") (pin "1") (pinfunction "S_1") (pintype "passive"))
      (node (ref "OC1") (pin "4") (pinfunction "C_4") (pintype "passive"))
      (node (ref "R8") (pin "1") (pinfunction "1_1") (pintype "passive"))
    )
    (net (code "132") (name "Net-(J17A-S)") (class "Default")
      (node (ref "J17") (pin "1") (pinfunction "S_1") (pintype "passive"))
      (node (ref "Q2") (pin "3") (pinfunction "D_3") (pintype "passive"))
      (node (ref "R9") (pin "1") (pinfunction "1_1") (pintype "passive"))
    )
    (net (code "133") (name "Net-(J18B-1)") (class "Default")
      (node (ref "J18") (pin "2") (pinfunction "1_2") (pintype "passive"))
      (node (ref "R65") (pin "2") (pinfunction "2_2") (pintype "passive"))
    )
    (net (code "134") (name "Net-(J18C-1)") (class "Default")
      (node (ref "J18") (pin "3") (pinfunction "1_3") (pintype "passive"))
      (node (ref "R63") (pin "2") (pinfunction "2_2") (pintype "passive"))
    )
    (net (code "135") (name "Net-(J18D-1)") (class "Default")
      (node (ref "J18") (pin "4") (pinfunction "1_4") (pintype "passive"))
      (node (ref "R64") (pin "2") (pinfunction "2_2") (pintype "passive"))
    )
    (net (code "136") (name "Net-(J20B-1)") (class "Default")
      (node (ref "J20") (pin "P2") (pinfunction "1_P2") (pintype "passive"))
      (node (ref "J20") (pin "P5") (pinfunction "1_P5") (pintype "passive"))
      (node (ref "J20") (pin "P8") (pinfunction "1_P8") (pintype "passive"))
      (node (ref "J21") (pin "P2") (pinfunction "1_P2") (pintype "passive"))
      (node (ref "J21") (pin "P5") (pinfunction "1_P5") (pintype "passive"))
      (node (ref "J21") (pin "P8") (pinfunction "1_P8") (pintype "passive"))
      (node (ref "J7") (pin "1") (pinfunction "S_1") (pintype "passive"))
      (node (ref "R71") (pin "1") (pinfunction "1_1") (pintype "passive"))
    )
    (net (code "137") (name "Net-(LED1-PadA)") (class "Default")
      (node (ref "LED1") (pin "A") (pinfunction "A_A") (pintype "passive"))
      (node (ref "R18") (pin "2") (pinfunction "2_2") (pintype "passive"))
    )
    (net (code "138") (name "Net-(LED2-PadA)") (class "Default")
      (node (ref "LED2") (pin "A") (pinfunction "A_A") (pintype "passive"))
      (node (ref "R19") (pin "2") (pinfunction "2_2") (pintype "passive"))
    )
    (net (code "139") (name "Net-(LED3-PadC)") (class "Default")
      (node (ref "LED3") (pin "C") (pinfunction "C_C") (pintype "passive"))
      (node (ref "R21") (pin "1") (pinfunction "1_1") (pintype "passive"))
    )
    (net (code "140") (name "Net-(LED4-PadC)") (class "Default")
      (node (ref "LED4") (pin "C") (pinfunction "C_C") (pintype "passive"))
      (node (ref "R22") (pin "1") (pinfunction "1_1") (pintype "passive"))
    )
    (net (code "141") (name "Net-(LED5-PadA)") (class "Default")
      (node (ref "LED5") (pin "A") (pinfunction "A_A") (pintype "passive"))
      (node (ref "R23") (pin "2") (pinfunction "2_2") (pintype "passive"))
    )
    (net (code "142") (name "Net-(LED6-PadA)") (class "Default")
      (node (ref "LED6") (pin "A") (pinfunction "A_A") (pintype "passive"))
      (node (ref "R63") (pin "1") (pinfunction "1_1") (pintype "passive"))
    )
    (net (code "143") (name "Net-(LED7-PadA)") (class "Default")
      (node (ref "LED7") (pin "A") (pinfunction "A_A") (pintype "passive"))
      (node (ref "R64") (pin "1") (pinfunction "1_1") (pintype "passive"))
    )
    (net (code "144") (name "Net-(LED8-PadC)") (class "Default")
      (node (ref "LED8") (pin "C") (pinfunction "C_C") (pintype "passive"))
      (node (ref "R65") (pin "1") (pinfunction "1_1") (pintype "passive"))
    )
    (net (code "145") (name "Net-(OC1-IN-A)") (class "Default")
      (node (ref "OC1") (pin "1") (pinfunction "IN-A_1") (pintype "passive"))
      (node (ref "R3") (pin "1") (pinfunction "1_1") (pintype "passive"))
    )
    (net (code "146") (name "Net-(OC2-IN-A)") (class "Default")
      (node (ref "OC2") (pin "1") (pinfunction "IN-A_1") (pintype "passive"))
      (node (ref "R75") (pin "1") (pinfunction "1_1") (pintype "passive"))
    )
    (net (code "147") (name "Net-(Q1-G)") (class "Default")
      (node (ref "D4") (pin "A") (pinfunction "A_A") (pintype "passive"))
      (node (ref "Q1") (pin "4") (pinfunction "G_4") (pintype "passive"))
      (node (ref "R4") (pin "1") (pinfunction "1_1") (pintype "passive"))
      (node (ref "R8") (pin "2") (pinfunction "2_2") (pintype "passive"))
    )
    (net (code "148") (name "Net-(Q2-G)") (class "Default")
      (node (ref "Q2") (pin "1") (pinfunction "G_1") (pintype "passive"))
      (node (ref "R5") (pin "1") (pinfunction "1_1") (pintype "passive"))
      (node (ref "R7") (pin "1") (pinfunction "1_1") (pintype "passive"))
    )
    (net (code "149") (name "Net-(Q3-G)") (class "Default")
      (node (ref "C42") (pin "2") (pinfunction "2_2") (pintype "passive"))
      (node (ref "D5") (pin "A") (pinfunction "A_A") (pintype "passive"))
      (node (ref "Q3") (pin "4") (pinfunction "G_4") (pintype "passive"))
      (node (ref "R6") (pin "1") (pinfunction "1_1") (pintype "passive"))
      (node (ref "R9") (pin "2") (pinfunction "2_2") (pintype "passive"))
    )
    (net (code "150") (name "Net-(Q4-G)") (class "Default")
      (node (ref "Q4") (pin "1") (pinfunction "G_1") (pintype "passive"))
      (node (ref "R36") (pin "2") (pinfunction "2_2") (pintype "passive"))
      (node (ref "R40") (pin "2") (pinfunction "2_2") (pintype "passive"))
    )
    (net (code "151") (name "Net-(Q5-G)") (class "Default")
      (node (ref "Q5") (pin "1") (pinfunction "G_1") (pintype "passive"))
      (node (ref "R37") (pin "2") (pinfunction "2_2") (pintype "passive"))
      (node (ref "R41") (pin "2") (pinfunction "2_2") (pintype "passive"))
    )
    (net (code "152") (name "Net-(Q6-G)") (class "Default")
      (node (ref "Q6") (pin "1") (pinfunction "G_1") (pintype "passive"))
      (node (ref "R38") (pin "2") (pinfunction "2_2") (pintype "passive"))
      (node (ref "R42") (pin "2") (pinfunction "2_2") (pintype "passive"))
    )
    (net (code "153") (name "Net-(Q7-G)") (class "Default")
      (node (ref "Q7") (pin "1") (pinfunction "G_1") (pintype "passive"))
      (node (ref "R39") (pin "2") (pinfunction "2_2") (pintype "passive"))
      (node (ref "R43") (pin "2") (pinfunction "2_2") (pintype "passive"))
    )
    (net (code "154") (name "Net-(SENS1-OUT)") (class "Default")
      (node (ref "R45") (pin "1") (pinfunction "1_1") (pintype "passive"))
      (node (ref "SENS1") (pin "2") (pinfunction "OUT_2") (pintype "output"))
    )
    (net (code "155") (name "Net-(SENS2-VOUT)") (class "Default")
      (node (ref "R44") (pin "1") (pinfunction "1_1") (pintype "passive"))
      (node (ref "SENS2") (pin "2") (pinfunction "VOUT_2") (pintype "output"))
    )
    (net (code "156") (name "Net-(TP1-P)") (class "Default")
      (node (ref "R52") (pin "1") (pinfunction "1_1") (pintype "passive"))
      (node (ref "TP1") (pin "1") (pinfunction "P_1") (pintype "passive"))
      (node (ref "U8") (pin "7") (pinfunction "WP_7") (pintype "bidirectional"))
    )
    (net (code "157") (name "Net-(TP22-P)") (class "Default")
      (node (ref "J5") (pin "22") (pinfunction "22_22") (pintype "passive"))
      (node (ref "TP22") (pin "1") (pinfunction "P_1") (pintype "passive"))
    )
    (net (code "158") (name "Net-(U1-VOUT)") (class "Default")
      (node (ref "R68") (pin "1") (pinfunction "1_1") (pintype "passive"))
      (node (ref "U1") (pin "6") (pinfunction "VOUT_6") (pintype "output"))
    )
    (net (code "159") (name "Net-(U2-VOUT)") (class "Default")
      (node (ref "R67") (pin "1") (pinfunction "1_1") (pintype "passive"))
      (node (ref "U2") (pin "6") (pinfunction "VOUT_6") (pintype "output"))
    )
    (net (code "160") (name "Net-(U3-IN+)") (class "Default")
      (node (ref "Q1") (pin "5") (pinfunction "D_5") (pintype "passive"))
      (node (ref "Q1") (pin "6") (pinfunction "D_6") (pintype "passive"))
      (node (ref "Q1") (pin "7") (pinfunction "D_7") (pintype "passive"))
      (node (ref "Q1") (pin "8") (pinfunction "D_8") (pintype "passive"))
      (node (ref "R10") (pin "1") (pinfunction "1_1") (pintype "passive"))
      (node (ref "R12") (pin "1") (pinfunction "1_1") (pintype "passive"))
      (node (ref "U3") (pin "4") (pinfunction "IN+_4") (pintype "input"))
    )
    (net (code "161") (name "Net-(U3-VOUT)") (class "Default")
      (node (ref "R69") (pin "1") (pinfunction "1_1") (pintype "passive"))
      (node (ref "U3") (pin "6") (pinfunction "VOUT_6") (pintype "output"))
    )
    (net (code "162") (name "Net-(U4-BOOT)") (class "Default")
      (node (ref "C12") (pin "1") (pinfunction "1_1") (pintype "passive"))
      (node (ref "U4") (pin "1") (pinfunction "BOOT_1") (pintype "bidirectional"))
    )
    (net (code "163") (name "Net-(U4-COMP)") (class "Default")
      (node (ref "C10") (pin "1") (pinfunction "1_1") (pintype "passive"))
      (node (ref "U4") (pin "6") (pinfunction "COMP_6") (pintype "bidirectional"))
    )
    (net (code "164") (name "Net-(U4-EN)") (class "Default")
      (node (ref "R13") (pin "2") (pinfunction "2_2") (pintype "passive"))
      (node (ref "U4") (pin "7") (pinfunction "EN_7") (pintype "bidirectional"))
    )
    (net (code "165") (name "Net-(U4-FB)") (class "Default")
      (node (ref "R16") (pin "1") (pinfunction "1_1") (pintype "passive"))
      (node (ref "R17") (pin "2") (pinfunction "2_2") (pintype "passive"))
      (node (ref "U4") (pin "5") (pinfunction "FB_5") (pintype "bidirectional"))
    )
    (net (code "166") (name "Net-(U4-SS)") (class "Default")
      (node (ref "C11") (pin "1") (pinfunction "1_1") (pintype "passive"))
      (node (ref "U4") (pin "8") (pinfunction "SS_8") (pintype "bidirectional"))
    )
    (net (code "167") (name "Net-(U4-SW)") (class "Default")
      (node (ref "C12") (pin "2") (pinfunction "2_2") (pintype "passive"))
      (node (ref "L1") (pin "1") (pinfunction "1_1") (pintype "passive"))
      (node (ref "U4") (pin "3") (pinfunction "SW_3") (pintype "bidirectional"))
    )
    (net (code "168") (name "Net-(U4-VIN)") (class "Default")
      (node (ref "C8") (pin "1") (pinfunction "1_1") (pintype "passive"))
      (node (ref "C9") (pin "1") (pinfunction "1_1") (pintype "passive"))
      (node (ref "D6") (pin "C") (pinfunction "C_C") (pintype "passive"))
      (node (ref "F1") (pin "2") (pinfunction "2_2") (pintype "passive"))
      (node (ref "R13") (pin "1") (pinfunction "1_1") (pintype "passive"))
      (node (ref "U4") (pin "2") (pinfunction "VIN_2") (pintype "bidirectional"))
    )
    (net (code "169") (name "Net-(U6-XTAL1)") (class "Default")
      (node (ref "C20") (pin "1") (pinfunction "1_1") (pintype "passive"))
      (node (ref "U6") (pin "34") (pinfunction "XTAL1_34") (pintype "input"))
      (node (ref "X1") (pin "1") (pinfunction "1_1") (pintype "passive"))
    )
    (net (code "170") (name "Net-(U6-XTAL2)") (class "Default")
      (node (ref "C19") (pin "1") (pinfunction "1_1") (pintype "passive"))
      (node (ref "U6") (pin "33") (pinfunction "XTAL2_33") (pintype "output"))
      (node (ref "X1") (pin "2") (pinfunction "2_2") (pintype "passive"))
    )
    (net (code "171") (name "Net-(U7-A8)") (class "Default")
      (node (ref "R62") (pin "1") (pinfunction "1_1") (pintype "passive"))
      (node (ref "U7") (pin "9") (pinfunction "A8_9") (pintype "bidirectional"))
    )
    (net (code "172") (name "Net-(U7-OE)") (class "Default")
      (node (ref "R47") (pin "1") (pinfunction "1_1") (pintype "passive"))
      (node (ref "R48") (pin "1") (pinfunction "1_1") (pintype "passive"))
      (node (ref "U7") (pin "10") (pinfunction "OE_10") (pintype "bidirectional"))
    )
    (net (code "173") (name "Net-(U8-A2)") (class "Default")
      (node (ref "R51") (pin "1") (pinfunction "1_1") (pintype "passive"))
      (node (ref "U8") (pin "3") (pinfunction "A2_3") (pintype "input"))
    )
    (net (code "174") (name "Net-(U9-IN-)") (class "Default")
      (node (ref "C39") (pin "+") (pinfunction "+_+") (pintype "passive"))
      (node (ref "J14") (pin "PWR1") (pinfunction "S_PWR1") (pintype "passive"))
      (node (ref "J14") (pin "PWR2") (pinfunction "S_PWR2") (pintype "passive"))
      (node (ref "R59") (pin "2") (pinfunction "2_2") (pintype "passive"))
      (node (ref "U9") (pin "5") (pinfunction "IN-_5") (pintype "input"))
    )
    (net (code "175") (name "Net-(U9-VOUT)") (class "Default")
      (node (ref "R49") (pin "1") (pinfunction "1_1") (pintype "passive"))
      (node (ref "U9") (pin "6") (pinfunction "VOUT_6") (pintype "output"))
    )
    (net (code "176") (name "Net-(U10-IN-)") (class "Default")
      (node (ref "C40") (pin "+") (pinfunction "+_+") (pintype "passive"))
      (node (ref "J15") (pin "PWR1") (pinfunction "S_PWR1") (pintype "passive"))
      (node (ref "J15") (pin "PWR2") (pinfunction "S_PWR2") (pintype "passive"))
      (node (ref "R60") (pin "2") (pinfunction "2_2") (pintype "passive"))
      (node (ref "U10") (pin "5") (pinfunction "IN-_5") (pintype "input"))
    )
    (net (code "177") (name "Net-(U10-VOUT)") (class "Default")
      (node (ref "R50") (pin "1") (pinfunction "1_1") (pintype "passive"))
      (node (ref "U10") (pin "6") (pinfunction "VOUT_6") (pintype "output"))
    )
    (net (code "178") (name "Net-(U11-IN-)") (class "Default")
      (node (ref "C41") (pin "+") (pinfunction "+_+") (pintype "passive"))
      (node (ref "J16") (pin "PWR1") (pinfunction "S_PWR1") (pintype "passive"))
      (node (ref "J16") (pin "PWR2") (pinfunction "S_PWR2") (pintype "passive"))
      (node (ref "R61") (pin "2") (pinfunction "2_2") (pintype "passive"))
      (node (ref "U11") (pin "5") (pinfunction "IN-_5") (pintype "input"))
    )
    (net (code "179") (name "Net-(U11-VOUT)") (class "Default")
      (node (ref "R66") (pin "1") (pinfunction "1_1") (pintype "passive"))
      (node (ref "U11") (pin "6") (pinfunction "VOUT_6") (pintype "output"))
    )
    (net (code "180") (name "PWM_1+") (class "Default")
      (node (ref "D7") (pin "C") (pinfunction "C_C") (pintype "passive"))
      (node (ref "J1") (pin "1") (pinfunction "1_1") (pintype "passive"))
      (node (ref "R24") (pin "2") (pinfunction "2_2") (pintype "passive"))
      (node (ref "R25") (pin "2") (pinfunction "2_2") (pintype "passive"))
      (node (ref "R26") (pin "2") (pinfunction "2_2") (pintype "passive"))
    )
    (net (code "181") (name "PWM_1-") (class "Default")
      (node (ref "D7") (pin "A") (pinfunction "A_A") (pintype "passive"))
      (node (ref "J1") (pin "2") (pinfunction "1_2") (pintype "passive"))
      (node (ref "Q4") (pin "3") (pinfunction "D_3") (pintype "passive"))
    )
    (net (code "182") (name "PWM_2+") (class "Default")
      (node (ref "D8") (pin "C") (pinfunction "C_C") (pintype "passive"))
      (node (ref "J1") (pin "3") (pinfunction "1_3") (pintype "passive"))
      (node (ref "R27") (pin "2") (pinfunction "2_2") (pintype "passive"))
      (node (ref "R28") (pin "2") (pinfunction "2_2") (pintype "passive"))
      (node (ref "R29") (pin "2") (pinfunction "2_2") (pintype "passive"))
    )
    (net (code "183") (name "PWM_2-") (class "Default")
      (node (ref "D8") (pin "A") (pinfunction "A_A") (pintype "passive"))
      (node (ref "J1") (pin "4") (pinfunction "1_4") (pintype "passive"))
      (node (ref "Q5") (pin "3") (pinfunction "D_3") (pintype "passive"))
    )
    (net (code "184") (name "PWM_3+") (class "Default")
      (node (ref "D9") (pin "C") (pinfunction "C_C") (pintype "passive"))
      (node (ref "J1") (pin "5") (pinfunction "1_5") (pintype "passive"))
      (node (ref "R30") (pin "2") (pinfunction "2_2") (pintype "passive"))
      (node (ref "R31") (pin "2") (pinfunction "2_2") (pintype "passive"))
      (node (ref "R32") (pin "2") (pinfunction "2_2") (pintype "passive"))
      (node (ref "R73") (pin "1") (pinfunction "1_1") (pintype "passive"))
    )
    (net (code "185") (name "PWM_3-") (class "Default")
      (node (ref "D9") (pin "A") (pinfunction "A_A") (pintype "passive"))
      (node (ref "J1") (pin "6") (pinfunction "1_6") (pintype "passive"))
      (node (ref "Q6") (pin "3") (pinfunction "D_3") (pintype "passive"))
      (node (ref "R74") (pin "1") (pinfunction "1_1") (pintype "passive"))
    )
    (net (code "186") (name "PWM_4+") (class "Default")
      (node (ref "D10") (pin "C") (pinfunction "C_C") (pintype "passive"))
      (node (ref "J1") (pin "7") (pinfunction "1_7") (pintype "passive"))
      (node (ref "R33") (pin "2") (pinfunction "2_2") (pintype "passive"))
      (node (ref "R34") (pin "2") (pinfunction "2_2") (pintype "passive"))
      (node (ref "R35") (pin "2") (pinfunction "2_2") (pintype "passive"))
    )
    (net (code "187") (name "PWM_4-") (class "Default")
      (node (ref "D10") (pin "A") (pinfunction "A_A") (pintype "passive"))
      (node (ref "J1") (pin "8") (pinfunction "1_8") (pintype "passive"))
      (node (ref "Q7") (pin "3") (pinfunction "D_3") (pintype "passive"))
    )
    (net (code "188") (name "RESET_N") (class "Default")
      (node (ref "J13") (pin "5") (pinfunction "5_5") (pintype "passive"))
      (node (ref "R20") (pin "2") (pinfunction "2_2") (pintype "passive"))
      (node (ref "U6") (pin "30") (pinfunction "RESET_30") (pintype "input"))
      (node (ref "U7") (pin "13") (pinfunction "B7_13") (pintype "bidirectional"))
    )
    (net (code "189") (name "TETHER_A") (class "Default")
      (node (ref "FB1") (pin "1") (pinfunction "1_1") (pintype "passive"))
      (node (ref "J10") (pin "1") (pinfunction "S_1") (pintype "passive"))
      (node (ref "J19") (pin "1") (pinfunction "1_1") (pintype "passive"))
      (node (ref "J19") (pin "2") (pinfunction "1_2") (pintype "passive"))
      (node (ref "J5") (pin "18") (pinfunction "18_18") (pintype "passive"))
    )
    (net (code "190") (name "TETHER_B") (class "Default")
      (node (ref "C5") (pin "2") (pinfunction "2_2") (pintype "passive"))
      (node (ref "J10") (pin "3") (pinfunction "S_3") (pintype "passive"))
      (node (ref "J19") (pin "5") (pinfunction "1_5") (pintype "passive"))
      (node (ref "J19") (pin "6") (pinfunction "1_6") (pintype "passive"))
      (node (ref "J5") (pin "19") (pinfunction "19_19") (pintype "passive"))
      (node (ref "OC1") (pin "2") (pinfunction "IN-B_2") (pintype "passive"))
      (node (ref "OC2") (pin "2") (pinfunction "IN-B_2") (pintype "passive"))
    )
    (net (code "191") (name "TP20") (class "Default")
      (node (ref "J5") (pin "20") (pinfunction "20_20") (pintype "passive"))
      (node (ref "R73") (pin "2") (pinfunction "2_2") (pintype "passive"))
      (node (ref "TP20") (pin "1") (pinfunction "P_1") (pintype "passive"))
    )
    (net (code "192") (name "TP21") (class "Default")
      (node (ref "J5") (pin "21") (pinfunction "21_21") (pintype "passive"))
      (node (ref "R74") (pin "2") (pinfunction "2_2") (pintype "passive"))
      (node (ref "TP21") (pin "1") (pinfunction "P_1") (pintype "passive"))
    )
    (net (code "193") (name "TP23") (class "Default")
      (node (ref "J5") (pin "23") (pinfunction "23_23") (pintype "passive"))
      (node (ref "R70") (pin "2") (pinfunction "2_2") (pintype "passive"))
      (node (ref "TP23") (pin "1") (pinfunction "P_1") (pintype "passive"))
    )
    (net (code "194") (name "TP24") (class "Default")
      (node (ref "J5") (pin "24") (pinfunction "24_24") (pintype "passive"))
      (node (ref "R71") (pin "2") (pinfunction "2_2") (pintype "passive"))
      (node (ref "TP24") (pin "1") (pinfunction "P_1") (pintype "passive"))
    )
    (net (code "195") (name "TP25") (class "Default")
      (node (ref "J5") (pin "25") (pinfunction "25_25") (pintype "passive"))
      (node (ref "R72") (pin "2") (pinfunction "2_2") (pintype "passive"))
      (node (ref "TP25") (pin "1") (pinfunction "P_1") (pintype "passive"))
    )
    (net (code "196") (name "V_BAT") (class "Default")
      (node (ref "F1") (pin "1") (pinfunction "1_1") (pintype "passive"))
      (node (ref "R12") (pin "2") (pinfunction "2_2") (pintype "passive"))
      (node (ref "R26") (pin "1") (pinfunction "1_1") (pintype "passive"))
      (node (ref "R29") (pin "1") (pinfunction "1_1") (pintype "passive"))
      (node (ref "R32") (pin "1") (pinfunction "1_1") (pintype "passive"))
      (node (ref "R35") (pin "1") (pinfunction "1_1") (pintype "passive"))
      (node (ref "U3") (pin "5") (pinfunction "IN-_5") (pintype "input"))
    )
    (net (code "197") (name "unconnected-(J10B-S-Pad2)") (class "Default")
      (node (ref "J10") (pin "2") (pinfunction "S_2") (pintype "passive"))
    )
    (net (code "198") (name "unconnected-(J19C-1-Pad3)") (class "Default")
      (node (ref "J19") (pin "3") (pinfunction "1_3") (pintype "passive"))
    )
    (net (code "199") (name "unconnected-(J19D-1-Pad4)") (class "Default")
      (node (ref "J19") (pin "4") (pinfunction "1_4") (pintype "passive"))
    )
    (net (code "200") (name "unconnected-(SENS1-PadPAD)") (class "Default")
      (node (ref "SENS1") (pin "PAD") (pinfunction "PAD_PAD") (pintype "bidirectional"))
    )
    (net (code "201") (name "unconnected-(U6-(CLKO{slash}ICP3{slash}INT7)PE7-Pad9)") (class "Default")
      (node (ref "U6") (pin "9") (pinfunction "(CLKO/ICP3/INT7)PE7_9") (pintype "bidirectional"))
    )
    (net (code "202") (name "unconnected-(U6-(ICP1)PD4-Pad47)") (class "Default")
      (node (ref "U6") (pin "47") (pinfunction "(ICP1)PD4_47") (pintype "bidirectional"))
    )
    (net (code "203") (name "unconnected-(U6-(T1)PD6-Pad49)") (class "Default")
      (node (ref "U6") (pin "49") (pinfunction "(T1)PD6_49") (pintype "bidirectional"))
    )
    (net (code "204") (name "unconnected-(U6-(T3{slash}INT6)PE6-Pad8)") (class "Default")
      (node (ref "U6") (pin "8") (pinfunction "(T3/INT6)PE6_8") (pintype "bidirectional"))
    )
    (net (code "205") (name "unconnected-(U6-(TOSC1)PG4-Pad29)") (class "Default")
      (node (ref "U6") (pin "29") (pinfunction "(TOSC1)PG4_29") (pintype "bidirectional"))
    )
    (net (code "206") (name "unconnected-(U6-(TOSC2)PG3-Pad28)") (class "Default")
      (node (ref "U6") (pin "28") (pinfunction "(TOSC2)PG3_28") (pintype "bidirectional"))
    )
    (net (code "207") (name "unconnected-(U6-(XCK0{slash}AIN0)PE2-Pad4)") (class "Default")
      (node (ref "U6") (pin "4") (pinfunction "(XCK0/AIN0)PE2_4") (pintype "bidirectional"))
    )
    (net (code "208") (name "unconnected-(U6-(XCK1)PD5-Pad48)") (class "Default")
      (node (ref "U6") (pin "48") (pinfunction "(XCK1)PD5_48") (pintype "bidirectional"))
    )
    (net (code "209") (name "unconnected-(U6-PH2(XCK2)-Pad14)") (class "Default")
      (node (ref "U6") (pin "14") (pinfunction "PH2(XCK2)_14") (pintype "bidirectional"))
    )
    (net (code "210") (name "unconnected-(U6-PH7(T4)-Pad27)") (class "Default")
      (node (ref "U6") (pin "27") (pinfunction "PH7(T4)_27") (pintype "bidirectional"))
    )
    (net (code "211") (name "unconnected-(U6-PJ2(XCK3{slash}PCINT11)-Pad65)") (class "Default")
      (node (ref "U6") (pin "65") (pinfunction "PJ2(XCK3/PCINT11)_65") (pintype "bidirectional"))
    )
    (net (code "212") (name "unconnected-(U6-PJ3(PCINT12)-Pad66)") (class "Default")
      (node (ref "U6") (pin "66") (pinfunction "PJ3(PCINT12)_66") (pintype "bidirectional"))
    )
    (net (code "213") (name "unconnected-(U6-PJ4(PCINT13)-Pad67)") (class "Default")
      (node (ref "U6") (pin "67") (pinfunction "PJ4(PCINT13)_67") (pintype "bidirectional"))
    )
    (net (code "214") (name "unconnected-(U6-PJ5(PCINT14)-Pad68)") (class "Default")
      (node (ref "U6") (pin "68") (pinfunction "PJ5(PCINT14)_68") (pintype "bidirectional"))
    )
    (net (code "215") (name "unconnected-(U6-PJ6(PCINT15)-Pad69)") (class "Default")
      (node (ref "U6") (pin "69") (pinfunction "PJ6(PCINT15)_69") (pintype "bidirectional"))
    )
    (net (code "216") (name "unconnected-(U6-PJ7-Pad79)") (class "Default")
      (node (ref "U6") (pin "79") (pinfunction "PJ7_79") (pintype "bidirectional"))
    )
    (net (code "217") (name "unconnected-(U7-B8-Pad12)") (class "Default")
      (node (ref "U7") (pin "12") (pinfunction "B8_12") (pintype "bidirectional"))
    )
  )
)
